# Daughter_Card_v7_fixed.net
KiCad netlist of a schematic drawn in EAGLE
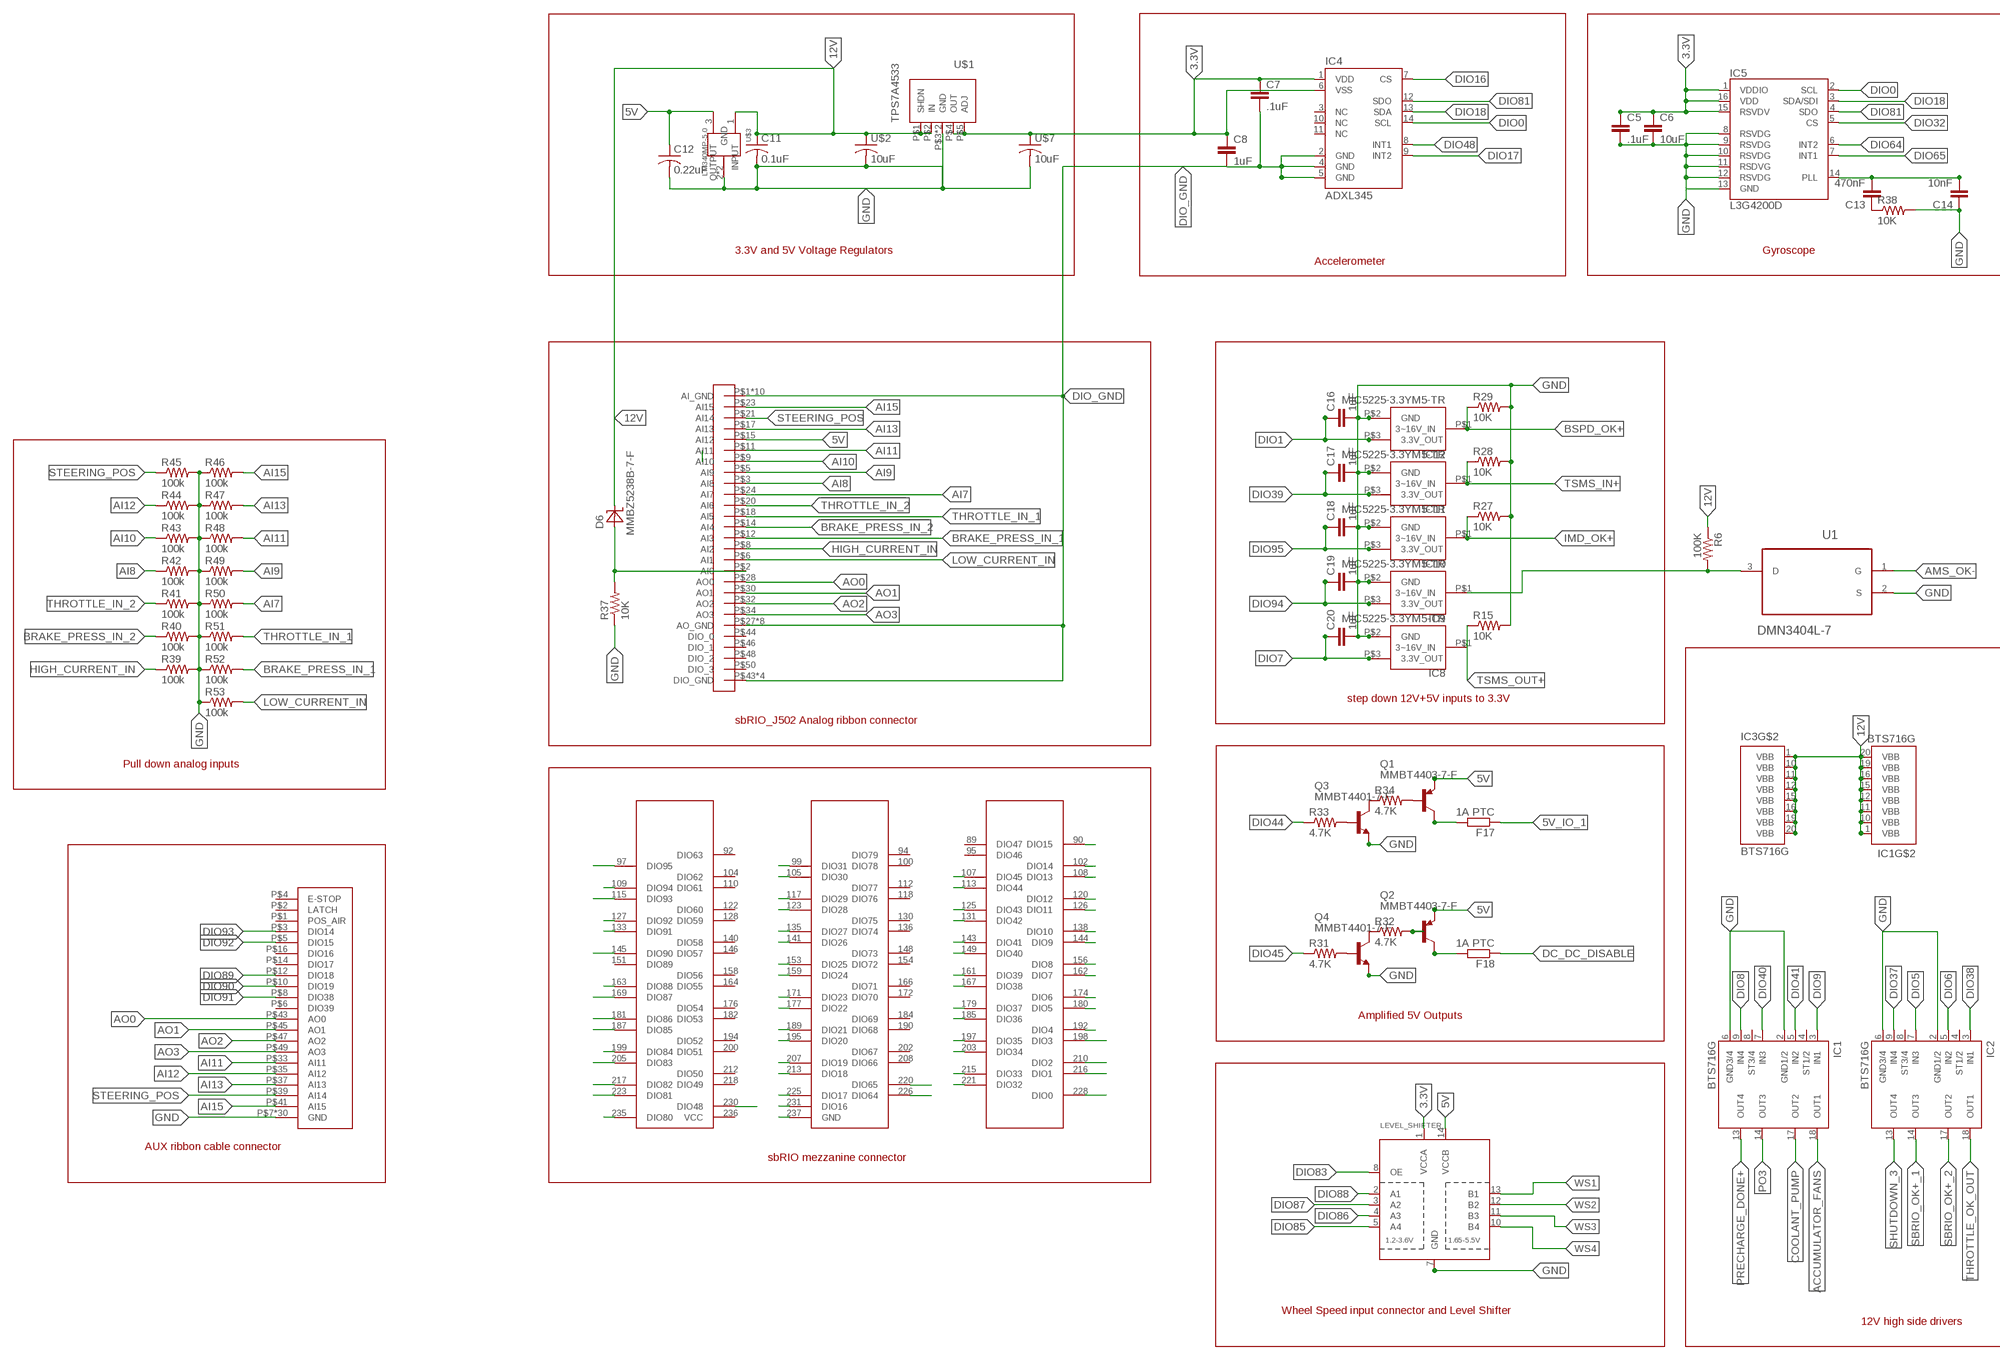
[diagram p0: schematic, sheet 1, part 1 of 2]
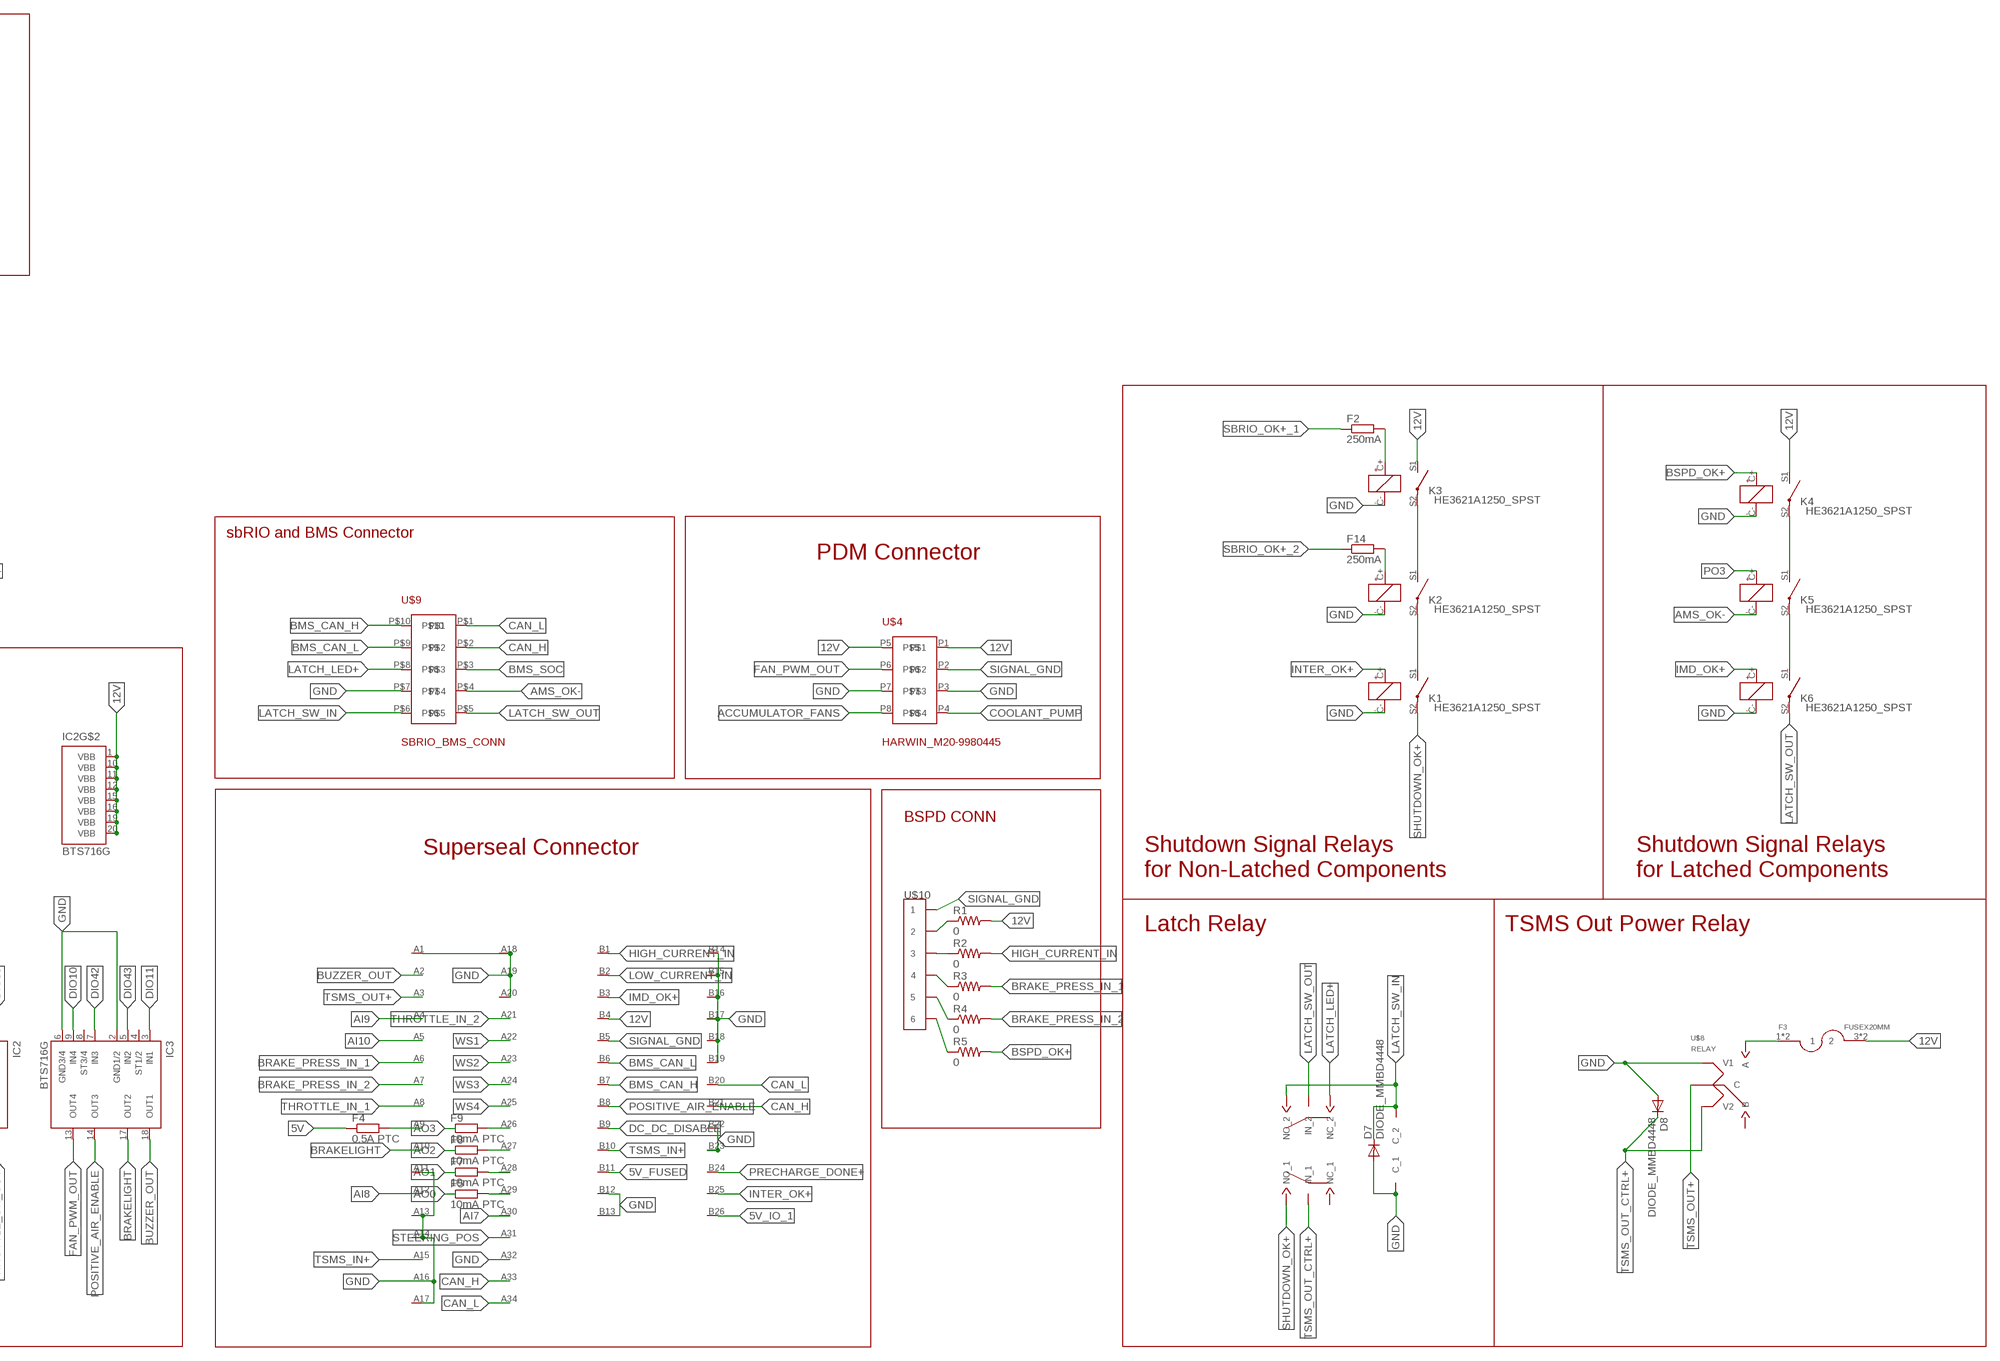
[diagram p1: schematic, sheet 1, part 2 of 2]

(export (version "E")
  (design (tool "Eeschema 10.0.6"))
  (components
    (comp (ref "C5")
      (value ".1uF")
      (footprint "eagle-import:0603-CAP")
      (libsource (lib "eagle-import") (part "CAP0603-CAP"))
    )
    (comp (ref "C6")
      (value "10uF")
      (footprint "eagle-import:0603-CAP")
      (libsource (lib "eagle-import") (part "CAP0603-CAP"))
    )
    (comp (ref "C7")
      (value ".1uF")
      (footprint "eagle-import:0603-CAP")
      (libsource (lib "eagle-import") (part "CAP0603-CAP"))
    )
    (comp (ref "C8")
      (value "1uF")
      (footprint "eagle-import:0603-CAP")
      (libsource (lib "eagle-import") (part "CAP0603-CAP"))
    )
    (comp (ref "C11")
      (value "0.1uF")
      (footprint "eagle-import:C1206")
      (libsource (lib "eagle-import") (part "C-USC1206"))
    )
    (comp (ref "C12")
      (value "0.22uF")
      (footprint "eagle-import:C1206")
      (libsource (lib "eagle-import") (part "C-USC1206"))
    )
    (comp (ref "C13")
      (value "470nF")
      (footprint "eagle-import:0603-CAP")
      (libsource (lib "eagle-import") (part "CAP0603-CAP"))
    )
    (comp (ref "C14")
      (value "10nF")
      (footprint "eagle-import:0603-CAP")
      (libsource (lib "eagle-import") (part "CAP0603-CAP"))
    )
    (comp (ref "C16")
      (value "1uF")
      (footprint "eagle-import:0603-CAP")
      (libsource (lib "eagle-import") (part "CAP0603-CAP"))
    )
    (comp (ref "C17")
      (value "1uF")
      (footprint "eagle-import:0603-CAP")
      (libsource (lib "eagle-import") (part "CAP0603-CAP"))
    )
    (comp (ref "C18")
      (value "1uF")
      (footprint "eagle-import:0603-CAP")
      (libsource (lib "eagle-import") (part "CAP0603-CAP"))
    )
    (comp (ref "C19")
      (value "1uF")
      (footprint "eagle-import:0603-CAP")
      (libsource (lib "eagle-import") (part "CAP0603-CAP"))
    )
    (comp (ref "C20")
      (value "1uF")
      (footprint "eagle-import:0603-CAP")
      (libsource (lib "eagle-import") (part "CAP0603-CAP"))
    )
    (comp (ref "D6")
      (value "MMBZ5238B-7-F")
      (footprint "eagle-import:SOT-23-3")
      (libsource (lib "eagle-import") (part "MMBZ5238B-7-F"))
    )
    (comp (ref "D7")
      (value "DIODE_MMBD4448")
      (footprint "eagle-import:SOT-23-3")
      (libsource (lib "eagle-import") (part "DIODE_MMBD4448"))
    )
    (comp (ref "D8")
      (value "DIODE_MMBD4448")
      (footprint "eagle-import:SOT-23-3")
      (libsource (lib "eagle-import") (part "DIODE_MMBD4448"))
    )
    (comp (ref "F2")
      (value "250mA")
      (footprint "eagle-import:R0603")
      (libsource (lib "eagle-import") (part "R-EU_R0603"))
    )
    (comp (ref "F3")
      (value "FUSEX20MM")
      (footprint "eagle-import:FUSE_5MM")
      (libsource (lib "eagle-import") (part "FUSEX20MM"))
    )
    (comp (ref "F4")
      (value "0.5A PTC")
      (footprint "eagle-import:R0603")
      (libsource (lib "eagle-import") (part "R-EU_R0603"))
    )
    (comp (ref "F5")
      (value "10mA PTC")
      (footprint "eagle-import:R0603")
      (libsource (lib "eagle-import") (part "R-EU_R0603"))
    )
    (comp (ref "F7")
      (value "10mA PTC")
      (footprint "eagle-import:R0603")
      (libsource (lib "eagle-import") (part "R-EU_R0603"))
    )
    (comp (ref "F8")
      (value "10mA PTC")
      (footprint "eagle-import:R0603")
      (libsource (lib "eagle-import") (part "R-EU_R0603"))
    )
    (comp (ref "F9")
      (value "10mA PTC")
      (footprint "eagle-import:R0603")
      (libsource (lib "eagle-import") (part "R-EU_R0603"))
    )
    (comp (ref "F14")
      (value "250mA")
      (footprint "eagle-import:R0603")
      (libsource (lib "eagle-import") (part "R-EU_R0603"))
    )
    (comp (ref "F17")
      (value "1A PTC")
      (footprint "eagle-import:R0603")
      (libsource (lib "eagle-import") (part "R-EU_R0603"))
    )
    (comp (ref "F18")
      (value "1A PTC")
      (footprint "eagle-import:R0603")
      (libsource (lib "eagle-import") (part "R-EU_R0603"))
    )
    (comp (ref "IC1")
      (value "BTS716G")
      (footprint "eagle-import:PG-DSO-20")
      (libsource (lib "eagle-import") (part "BTS716G"))
    )
    (comp (ref "IC2")
      (value "BTS716G")
      (footprint "eagle-import:PG-DSO-20")
      (libsource (lib "eagle-import") (part "BTS716G"))
    )
    (comp (ref "IC3")
      (value "BTS716G")
      (footprint "eagle-import:PG-DSO-20")
      (libsource (lib "eagle-import") (part "BTS716G"))
    )
    (comp (ref "IC4")
      (value "ADXL345")
      (footprint "eagle-import:LGA14")
      (libsource (lib "eagle-import") (part "ADXL345"))
    )
    (comp (ref "IC5")
      (value "L3G4200D")
      (footprint "eagle-import:LGA16-4X4")
      (libsource (lib "eagle-import") (part "L3G4200D"))
    )
    (comp (ref "IC8")
      (value "MIC5225-3.3YM5-TR")
      (footprint "eagle-import:SOT-23-3")
      (libsource (lib "eagle-import") (part "MIC5225-3.3YM5-TR"))
    )
    (comp (ref "IC9")
      (value "MIC5225-3.3YM5-TR")
      (footprint "eagle-import:SOT-23-3")
      (libsource (lib "eagle-import") (part "MIC5225-3.3YM5-TR"))
    )
    (comp (ref "IC10")
      (value "MIC5225-3.3YM5-TR")
      (footprint "eagle-import:SOT-23-3")
      (libsource (lib "eagle-import") (part "MIC5225-3.3YM5-TR"))
    )
    (comp (ref "IC11")
      (value "MIC5225-3.3YM5-TR")
      (footprint "eagle-import:SOT-23-3")
      (libsource (lib "eagle-import") (part "MIC5225-3.3YM5-TR"))
    )
    (comp (ref "IC12")
      (value "MIC5225-3.3YM5-TR")
      (footprint "eagle-import:SOT-23-3")
      (libsource (lib "eagle-import") (part "MIC5225-3.3YM5-TR"))
    )
    (comp (ref "K1")
      (value "HE3621A1250_SPST")
      (footprint "eagle-import:HE3621A1250_SPST")
      (libsource (lib "eagle-import") (part "HE3621A1250_SPST"))
    )
    (comp (ref "K2")
      (value "HE3621A1250_SPST")
      (footprint "eagle-import:HE3621A1250_SPST")
      (libsource (lib "eagle-import") (part "HE3621A1250_SPST"))
    )
    (comp (ref "K3")
      (value "HE3621A1250_SPST")
      (footprint "eagle-import:HE3621A1250_SPST")
      (libsource (lib "eagle-import") (part "HE3621A1250_SPST"))
    )
    (comp (ref "K4")
      (value "HE3621A1250_SPST")
      (footprint "eagle-import:HE3621A1250_SPST")
      (libsource (lib "eagle-import") (part "HE3621A1250_SPST"))
    )
    (comp (ref "K5")
      (value "HE3621A1250_SPST")
      (footprint "eagle-import:HE3621A1250_SPST")
      (libsource (lib "eagle-import") (part "HE3621A1250_SPST"))
    )
    (comp (ref "K6")
      (value "HE3621A1250_SPST")
      (footprint "eagle-import:HE3621A1250_SPST")
      (libsource (lib "eagle-import") (part "HE3621A1250_SPST"))
    )
    (comp (ref "LATCH_U7")
      (value "JW2SN-DC12V")
      (footprint "eagle-import:DPDT_JW2_FORM_C")
      (libsource (lib "eagle-import") (part "JW2SN-DC12V"))
    )
    (comp (ref "LEVEL_SHIFTER")
      (value "TXB0104PWR")
      (footprint "eagle-import:TSSOP14")
      (libsource (lib "eagle-import") (part "TXB0104PWR"))
    )
    (comp (ref "Q1")
      (value "MMBT4403-7-F")
      (footprint "eagle-import:SOT-23-3")
      (libsource (lib "eagle-import") (part "MMBT4403-7-F"))
    )
    (comp (ref "Q2")
      (value "MMBT4403-7-F")
      (footprint "eagle-import:SOT-23-3")
      (libsource (lib "eagle-import") (part "MMBT4403-7-F"))
    )
    (comp (ref "Q3")
      (value "MMBT4401-7-F")
      (footprint "eagle-import:SOT-23-3")
      (libsource (lib "eagle-import") (part "MMBT4401-7-F"))
    )
    (comp (ref "Q4")
      (value "MMBT4401-7-F")
      (footprint "eagle-import:SOT-23-3")
      (libsource (lib "eagle-import") (part "MMBT4401-7-F"))
    )
    (comp (ref "R1")
      (value "0")
      (footprint "eagle-import:M0805")
      (libsource (lib "eagle-import") (part "resistor_R-US_M0805"))
    )
    (comp (ref "R2")
      (value "0")
      (footprint "eagle-import:M0805")
      (libsource (lib "eagle-import") (part "resistor_R-US_M0805"))
    )
    (comp (ref "R3")
      (value "0")
      (footprint "eagle-import:M0805")
      (libsource (lib "eagle-import") (part "resistor_R-US_M0805"))
    )
    (comp (ref "R4")
      (value "0")
      (footprint "eagle-import:M0805")
      (libsource (lib "eagle-import") (part "resistor_R-US_M0805"))
    )
    (comp (ref "R5")
      (value "0")
      (footprint "eagle-import:M0805")
      (libsource (lib "eagle-import") (part "resistor_R-US_M0805"))
    )
    (comp (ref "R6")
      (value "100K")
      (footprint "eagle-import:R0603")
      (libsource (lib "eagle-import") (part "R-US_R0603"))
    )
    (comp (ref "R15")
      (value "10K")
      (footprint "eagle-import:R0603")
      (libsource (lib "eagle-import") (part "resistor_R-US_R0603"))
    )
    (comp (ref "R27")
      (value "10K")
      (footprint "eagle-import:R0603")
      (libsource (lib "eagle-import") (part "resistor_R-US_R0603"))
    )
    (comp (ref "R28")
      (value "10K")
      (footprint "eagle-import:R0603")
      (libsource (lib "eagle-import") (part "resistor_R-US_R0603"))
    )
    (comp (ref "R29")
      (value "10K")
      (footprint "eagle-import:R0603")
      (libsource (lib "eagle-import") (part "resistor_R-US_R0603"))
    )
    (comp (ref "R31")
      (value "4.7K")
      (footprint "eagle-import:R0603")
      (libsource (lib "eagle-import") (part "resistor_R-US_R0603"))
    )
    (comp (ref "R32")
      (value "4.7K")
      (footprint "eagle-import:R0603")
      (libsource (lib "eagle-import") (part "resistor_R-US_R0603"))
    )
    (comp (ref "R33")
      (value "4.7K")
      (footprint "eagle-import:R0603")
      (libsource (lib "eagle-import") (part "resistor_R-US_R0603"))
    )
    (comp (ref "R34")
      (value "4.7K")
      (footprint "eagle-import:R0603")
      (libsource (lib "eagle-import") (part "resistor_R-US_R0603"))
    )
    (comp (ref "R37")
      (value "10K")
      (footprint "eagle-import:R0603")
      (libsource (lib "eagle-import") (part "resistor_R-US_R0603"))
    )
    (comp (ref "R38")
      (value "10K")
      (footprint "eagle-import:R0603")
      (libsource (lib "eagle-import") (part "resistor_R-US_R0603"))
    )
    (comp (ref "R39")
      (value "100k")
      (footprint "eagle-import:R0603")
      (libsource (lib "eagle-import") (part "resistor_R-US_R0603"))
    )
    (comp (ref "R40")
      (value "100k")
      (footprint "eagle-import:R0603")
      (libsource (lib "eagle-import") (part "resistor_R-US_R0603"))
    )
    (comp (ref "R41")
      (value "100k")
      (footprint "eagle-import:R0603")
      (libsource (lib "eagle-import") (part "resistor_R-US_R0603"))
    )
    (comp (ref "R42")
      (value "100k")
      (footprint "eagle-import:R0603")
      (libsource (lib "eagle-import") (part "resistor_R-US_R0603"))
    )
    (comp (ref "R43")
      (value "100k")
      (footprint "eagle-import:R0603")
      (libsource (lib "eagle-import") (part "resistor_R-US_R0603"))
    )
    (comp (ref "R44")
      (value "100k")
      (footprint "eagle-import:R0603")
      (libsource (lib "eagle-import") (part "resistor_R-US_R0603"))
    )
    (comp (ref "R45")
      (value "100k")
      (footprint "eagle-import:R0603")
      (libsource (lib "eagle-import") (part "resistor_R-US_R0603"))
    )
    (comp (ref "R46")
      (value "100k")
      (footprint "eagle-import:R0603")
      (libsource (lib "eagle-import") (part "resistor_R-US_R0603"))
    )
    (comp (ref "R47")
      (value "100k")
      (footprint "eagle-import:R0603")
      (libsource (lib "eagle-import") (part "resistor_R-US_R0603"))
    )
    (comp (ref "R48")
      (value "100k")
      (footprint "eagle-import:R0603")
      (libsource (lib "eagle-import") (part "resistor_R-US_R0603"))
    )
    (comp (ref "R49")
      (value "100k")
      (footprint "eagle-import:R0603")
      (libsource (lib "eagle-import") (part "resistor_R-US_R0603"))
    )
    (comp (ref "R50")
      (value "100k")
      (footprint "eagle-import:R0603")
      (libsource (lib "eagle-import") (part "resistor_R-US_R0603"))
    )
    (comp (ref "R51")
      (value "100k")
      (footprint "eagle-import:R0603")
      (libsource (lib "eagle-import") (part "resistor_R-US_R0603"))
    )
    (comp (ref "R52")
      (value "100k")
      (footprint "eagle-import:R0603")
      (libsource (lib "eagle-import") (part "resistor_R-US_R0603"))
    )
    (comp (ref "R53")
      (value "100k")
      (footprint "eagle-import:R0603")
      (libsource (lib "eagle-import") (part "resistor_R-US_R0603"))
    )
    (comp (ref "SBRIO_ANALOG")
      (value "SBRIO_MIO")
      (footprint "eagle-import:SBRIO_J502_J503")
      (libsource (lib "eagle-import") (part "SBRIO_MIO"))
    )
    (comp (ref "SBRIO_AUX")
      (value "SBRIO_AUX")
      (footprint "eagle-import:SBRIO_J502_J503")
      (libsource (lib "eagle-import") (part "SBRIO_AUX"))
    )
    (comp (ref "SBRIO_MEZZANINE")
      (value "SBRIO_RMC")
      (footprint "eagle-import:SEAM-40-XX.X-XX-06-X-A")
      (libsource (lib "eagle-import") (part "SBRIO_RMC"))
    )
    (comp (ref "U$1")
      (value "TPS7A4533")
      (footprint "eagle-import:TPS7A4533")
      (libsource (lib "eagle-import") (part "TPS7A4533"))
    )
    (comp (ref "U$2")
      (value "10uF")
      (footprint "eagle-import:C1206")
      (libsource (lib "eagle-import") (part "C-USC1206"))
    )
    (comp (ref "U$3")
      (value "LM340MP-5.0")
      (footprint "eagle-import:SOT-223-4")
      (libsource (lib "eagle-import") (part "LM340MP-5.0"))
    )
    (comp (ref "U$4")
      (value "HARWIN_M20-9980445")
      (footprint "eagle-import:HARWIN_M20-9980445")
      (libsource (lib "eagle-import") (part "HARWIN_M20-9980445"))
    )
    (comp (ref "U$6")
      (value "SUPERSEAL1.0_60POS")
      (footprint "eagle-import:SUPERSEAL1.0_60POS")
      (libsource (lib "eagle-import") (part "SUPERSEAL1.0_60POS"))
    )
    (comp (ref "U$7")
      (value "10uF")
      (footprint "eagle-import:C1206")
      (libsource (lib "eagle-import") (part "C-USC1206"))
    )
    (comp (ref "U$8")
      (value "RELAY")
      (footprint "eagle-import:RELAY")
      (libsource (lib "eagle-import") (part "RELAY"))
    )
    (comp (ref "U$9")
      (value "SBRIO_BMS_CONN")
      (footprint "eagle-import:SBRIO_W")
      (libsource (lib "eagle-import") (part "SBRIO_BMS_CONN"))
    )
    (comp (ref "U$10")
      (value "SULLINS_1MM_6P_HEADER")
      (footprint "eagle-import:SULLINS_1MM_HEADER")
      (libsource (lib "eagle-import") (part "SULLINS_1MM_6P_HEADER"))
    )
    (comp (ref "U1")
      (value "DMN3404L-7")
      (footprint "eagle-import:SOT95P235X112-3N")
      (libsource (lib "eagle-import") (part "DMN3404L-7"))
    )
  )
  (nets
    (net (code "1") (name "/VCC") (class "Default")
      (node (ref "SBRIO_MEZZANINE") (pin "236") (pinfunction "VCC_236") (pintype "power_in"))
    )
    (net (code "2") (name "3.3V") (class "Default")
      (node (ref "C5") (pin "1") (pinfunction "1_1") (pintype "passive"))
      (node (ref "C6") (pin "1") (pinfunction "1_1") (pintype "passive"))
      (node (ref "C7") (pin "1") (pinfunction "1_1") (pintype "passive"))
      (node (ref "C8") (pin "1") (pinfunction "1_1") (pintype "passive"))
      (node (ref "IC4") (pin "1") (pinfunction "VDD_1") (pintype "bidirectional"))
      (node (ref "IC4") (pin "6") (pinfunction "VSS_6") (pintype "bidirectional"))
      (node (ref "IC5") (pin "1") (pinfunction "VDDIO_1") (pintype "bidirectional"))
      (node (ref "IC5") (pin "15") (pinfunction "RSVDV_15") (pintype "bidirectional"))
      (node (ref "IC5") (pin "16") (pinfunction "VDD_16") (pintype "bidirectional"))
      (node (ref "LEVEL_SHIFTER") (pin "1") (pinfunction "VCCA_1") (pintype "bidirectional"))
      (node (ref "U$1") (pin "P$4") (pinfunction "OUT_P$4") (pintype "bidirectional"))
      (node (ref "U$1") (pin "P$5") (pinfunction "ADJ_P$5") (pintype "bidirectional"))
      (node (ref "U$7") (pin "1") (pinfunction "1_1") (pintype "passive"))
    )
    (net (code "3") (name "5V") (class "Default")
      (node (ref "C12") (pin "1") (pinfunction "1_1") (pintype "passive"))
      (node (ref "F4") (pin "1") (pinfunction "1_1") (pintype "passive"))
      (node (ref "LEVEL_SHIFTER") (pin "14") (pinfunction "VCCB_14") (pintype "bidirectional"))
      (node (ref "Q1") (pin "P$3") (pinfunction "E_P$3") (pintype "passive"))
      (node (ref "Q2") (pin "P$3") (pinfunction "E_P$3") (pintype "passive"))
      (node (ref "SBRIO_ANALOG") (pin "P$15") (pinfunction "AI12_P$15") (pintype "input"))
      (node (ref "U$3") (pin "3") (pinfunction "OUTPUT_3") (pintype "bidirectional"))
    )
    (net (code "4") (name "5V_FUSED") (class "Default")
      (node (ref "F4") (pin "2") (pinfunction "2_2") (pintype "passive"))
      (node (ref "U$6") (pin "A9") (pinfunction "A9_A9") (pintype "bidirectional"))
      (node (ref "U$6") (pin "B11") (pinfunction "B11_B11") (pintype "bidirectional"))
    )
    (net (code "5") (name "5V_IO_1") (class "Default")
      (node (ref "F17") (pin "1") (pinfunction "1_1") (pintype "passive"))
      (node (ref "U$6") (pin "B26") (pinfunction "B26_B26") (pintype "bidirectional"))
    )
    (net (code "6") (name "12V") (class "Default")
      (node (ref "C11") (pin "1") (pinfunction "1_1") (pintype "passive"))
      (node (ref "D6") (pin "P$1") (pinfunction "C_P$1") (pintype "passive"))
      (node (ref "F3") (pin "3") (pinfunction "2_3") (pintype "bidirectional"))
      (node (ref "F3") (pin "4") (pinfunction "2_4") (pintype "bidirectional"))
      (node (ref "IC1") (pin "1") (pinfunction "VBB_1") (pintype "power_in"))
      (node (ref "IC1") (pin "10") (pinfunction "VBB_10") (pintype "power_in"))
      (node (ref "IC1") (pin "11") (pinfunction "VBB_11") (pintype "power_in"))
      (node (ref "IC1") (pin "12") (pinfunction "VBB_12") (pintype "power_in"))
      (node (ref "IC1") (pin "15") (pinfunction "VBB_15") (pintype "power_in"))
      (node (ref "IC1") (pin "16") (pinfunction "VBB_16") (pintype "power_in"))
      (node (ref "IC1") (pin "19") (pinfunction "VBB_19") (pintype "power_in"))
      (node (ref "IC1") (pin "20") (pinfunction "VBB_20") (pintype "power_in"))
      (node (ref "IC2") (pin "1") (pinfunction "VBB_1") (pintype "power_in"))
      (node (ref "IC2") (pin "10") (pinfunction "VBB_10") (pintype "power_in"))
      (node (ref "IC2") (pin "11") (pinfunction "VBB_11") (pintype "power_in"))
      (node (ref "IC2") (pin "12") (pinfunction "VBB_12") (pintype "power_in"))
      (node (ref "IC2") (pin "15") (pinfunction "VBB_15") (pintype "power_in"))
      (node (ref "IC2") (pin "16") (pinfunction "VBB_16") (pintype "power_in"))
      (node (ref "IC2") (pin "19") (pinfunction "VBB_19") (pintype "power_in"))
      (node (ref "IC2") (pin "20") (pinfunction "VBB_20") (pintype "power_in"))
      (node (ref "IC3") (pin "1") (pinfunction "VBB_1") (pintype "power_in"))
      (node (ref "IC3") (pin "10") (pinfunction "VBB_10") (pintype "power_in"))
      (node (ref "IC3") (pin "11") (pinfunction "VBB_11") (pintype "power_in"))
      (node (ref "IC3") (pin "12") (pinfunction "VBB_12") (pintype "power_in"))
      (node (ref "IC3") (pin "15") (pinfunction "VBB_15") (pintype "power_in"))
      (node (ref "IC3") (pin "16") (pinfunction "VBB_16") (pintype "power_in"))
      (node (ref "IC3") (pin "19") (pinfunction "VBB_19") (pintype "power_in"))
      (node (ref "IC3") (pin "20") (pinfunction "VBB_20") (pintype "power_in"))
      (node (ref "K3") (pin "S1") (pinfunction "SW_1_S1") (pintype "passive"))
      (node (ref "K4") (pin "S1") (pinfunction "SW_1_S1") (pintype "passive"))
      (node (ref "R1") (pin "2") (pinfunction "2_2") (pintype "passive"))
      (node (ref "R6") (pin "1") (pinfunction "1_1") (pintype "passive"))
      (node (ref "U$1") (pin "P$1") (pinfunction "SHDN_P$1") (pintype "bidirectional"))
      (node (ref "U$1") (pin "P$2") (pinfunction "IN_P$2") (pintype "bidirectional"))
      (node (ref "U$2") (pin "1") (pinfunction "1_1") (pintype "passive"))
      (node (ref "U$3") (pin "1") (pinfunction "INPUT_1") (pintype "bidirectional"))
      (node (ref "U$4") (pin "P1") (pinfunction "P$1_P1") (pintype "bidirectional"))
      (node (ref "U$4") (pin "P5") (pinfunction "P$5_P5") (pintype "bidirectional"))
      (node (ref "U$6") (pin "B4") (pinfunction "B4_B4") (pintype "bidirectional"))
    )
    (net (code "7") (name "ACCUMULATOR_FANS") (class "Default")
      (node (ref "IC1") (pin "18") (pinfunction "OUT1_18") (pintype "output"))
      (node (ref "U$4") (pin "P8") (pinfunction "P$8_P8") (pintype "bidirectional"))
    )
    (net (code "8") (name "AI7") (class "Default")
      (node (ref "R50") (pin "2") (pinfunction "2_2") (pintype "passive"))
      (node (ref "SBRIO_ANALOG") (pin "P$24") (pinfunction "AI7_P$24") (pintype "input"))
      (node (ref "U$6") (pin "A30") (pinfunction "A30_A30") (pintype "bidirectional"))
    )
    (net (code "9") (name "AI8") (class "Default")
      (node (ref "R42") (pin "1") (pinfunction "1_1") (pintype "passive"))
      (node (ref "SBRIO_ANALOG") (pin "P$3") (pinfunction "AI8_P$3") (pintype "input"))
      (node (ref "U$6") (pin "A12") (pinfunction "A12_A12") (pintype "bidirectional"))
    )
    (net (code "10") (name "AI9") (class "Default")
      (node (ref "R49") (pin "2") (pinfunction "2_2") (pintype "passive"))
      (node (ref "SBRIO_ANALOG") (pin "P$5") (pinfunction "AI9_P$5") (pintype "input"))
      (node (ref "U$6") (pin "A4") (pinfunction "A4_A4") (pintype "bidirectional"))
    )
    (net (code "11") (name "AI10") (class "Default")
      (node (ref "R43") (pin "1") (pinfunction "1_1") (pintype "passive"))
      (node (ref "SBRIO_ANALOG") (pin "P$9") (pinfunction "AI10_P$9") (pintype "input"))
      (node (ref "U$6") (pin "A5") (pinfunction "A5_A5") (pintype "bidirectional"))
    )
    (net (code "12") (name "AI11") (class "Default")
      (node (ref "R48") (pin "2") (pinfunction "2_2") (pintype "passive"))
      (node (ref "SBRIO_ANALOG") (pin "P$11") (pinfunction "AI11_P$11") (pintype "input"))
      (node (ref "SBRIO_AUX") (pin "P$33") (pinfunction "AI11_P$33") (pintype "bidirectional"))
    )
    (net (code "13") (name "AI12") (class "Default")
      (node (ref "R44") (pin "1") (pinfunction "1_1") (pintype "passive"))
      (node (ref "SBRIO_AUX") (pin "P$35") (pinfunction "AI12_P$35") (pintype "bidirectional"))
    )
    (net (code "14") (name "AI13") (class "Default")
      (node (ref "R47") (pin "2") (pinfunction "2_2") (pintype "passive"))
      (node (ref "SBRIO_ANALOG") (pin "P$17") (pinfunction "AI13_P$17") (pintype "input"))
      (node (ref "SBRIO_AUX") (pin "P$37") (pinfunction "AI13_P$37") (pintype "bidirectional"))
    )
    (net (code "15") (name "AI15") (class "Default")
      (node (ref "R46") (pin "2") (pinfunction "2_2") (pintype "passive"))
      (node (ref "SBRIO_ANALOG") (pin "P$23") (pinfunction "AI15_P$23") (pintype "input"))
      (node (ref "SBRIO_AUX") (pin "P$41") (pinfunction "AI15_P$41") (pintype "bidirectional"))
    )
    (net (code "16") (name "AMS_OK-") (class "Default")
      (node (ref "K5") (pin "C-") (pinfunction "C-_C-") (pintype "passive"))
      (node (ref "U$9") (pin "P$4") (pinfunction "P$4_P$4") (pintype "bidirectional"))
      (node (ref "U1") (pin "1") (pinfunction "G_1") (pintype "input"))
    )
    (net (code "17") (name "AO0") (class "Default")
      (node (ref "F5") (pin "1") (pinfunction "1_1") (pintype "passive"))
      (node (ref "SBRIO_ANALOG") (pin "P$28") (pinfunction "AO0_P$28") (pintype "output"))
      (node (ref "SBRIO_AUX") (pin "P$43") (pinfunction "AO0_P$43") (pintype "bidirectional"))
    )
    (net (code "18") (name "AO1") (class "Default")
      (node (ref "F7") (pin "1") (pinfunction "1_1") (pintype "passive"))
      (node (ref "SBRIO_ANALOG") (pin "P$30") (pinfunction "AO1_P$30") (pintype "output"))
      (node (ref "SBRIO_AUX") (pin "P$45") (pinfunction "AO1_P$45") (pintype "bidirectional"))
    )
    (net (code "19") (name "AO2") (class "Default")
      (node (ref "F8") (pin "1") (pinfunction "1_1") (pintype "passive"))
      (node (ref "SBRIO_ANALOG") (pin "P$32") (pinfunction "AO2_P$32") (pintype "output"))
      (node (ref "SBRIO_AUX") (pin "P$47") (pinfunction "AO2_P$47") (pintype "bidirectional"))
    )
    (net (code "20") (name "AO3") (class "Default")
      (node (ref "F9") (pin "1") (pinfunction "1_1") (pintype "passive"))
      (node (ref "SBRIO_ANALOG") (pin "P$34") (pinfunction "AO3_P$34") (pintype "output"))
      (node (ref "SBRIO_AUX") (pin "P$49") (pinfunction "AO3_P$49") (pintype "bidirectional"))
    )
    (net (code "21") (name "BMS_CAN_H") (class "Default")
      (node (ref "U$6") (pin "B7") (pinfunction "B7_B7") (pintype "bidirectional"))
      (node (ref "U$9") (pin "P$10") (pinfunction "P$10_P$10") (pintype "bidirectional"))
    )
    (net (code "22") (name "BMS_CAN_L") (class "Default")
      (node (ref "U$6") (pin "B6") (pinfunction "B6_B6") (pintype "bidirectional"))
      (node (ref "U$9") (pin "P$9") (pinfunction "P$9_P$9") (pintype "bidirectional"))
    )
    (net (code "23") (name "BMS_SOC") (class "Default")
      (node (ref "U$9") (pin "P$3") (pinfunction "P$3_P$3") (pintype "bidirectional"))
    )
    (net (code "24") (name "BRAKELIGHT") (class "Default")
      (node (ref "IC3") (pin "17") (pinfunction "OUT2_17") (pintype "output"))
      (node (ref "U$6") (pin "A10") (pinfunction "A10_A10") (pintype "bidirectional"))
    )
    (net (code "25") (name "BRAKE_PRESS_IN_1") (class "Default")
      (node (ref "R3") (pin "2") (pinfunction "2_2") (pintype "passive"))
      (node (ref "R52") (pin "2") (pinfunction "2_2") (pintype "passive"))
      (node (ref "SBRIO_ANALOG") (pin "P$12") (pinfunction "AI3_P$12") (pintype "input"))
      (node (ref "U$6") (pin "A6") (pinfunction "A6_A6") (pintype "bidirectional"))
    )
    (net (code "26") (name "BRAKE_PRESS_IN_2") (class "Default")
      (node (ref "R4") (pin "2") (pinfunction "2_2") (pintype "passive"))
      (node (ref "R40") (pin "1") (pinfunction "1_1") (pintype "passive"))
      (node (ref "SBRIO_ANALOG") (pin "P$14") (pinfunction "AI4_P$14") (pintype "input"))
      (node (ref "U$6") (pin "A7") (pinfunction "A7_A7") (pintype "bidirectional"))
    )
    (net (code "27") (name "BSPD_OK+") (class "Default")
      (node (ref "IC12") (pin "P$1") (pinfunction "3~{16V_IN}_P$1") (pintype "bidirectional"))
      (node (ref "K4") (pin "C+") (pinfunction "C+_C+") (pintype "passive"))
      (node (ref "R29") (pin "1") (pinfunction "1_1") (pintype "passive"))
      (node (ref "R5") (pin "2") (pinfunction "2_2") (pintype "passive"))
    )
    (net (code "28") (name "BUZZER_OUT") (class "Default")
      (node (ref "IC3") (pin "18") (pinfunction "OUT1_18") (pintype "output"))
      (node (ref "U$6") (pin "A2") (pinfunction "A2_A2") (pintype "bidirectional"))
    )
    (net (code "29") (name "CAN_H") (class "Default")
      (node (ref "U$6") (pin "A33") (pinfunction "A33_A33") (pintype "bidirectional"))
      (node (ref "U$6") (pin "B21") (pinfunction "B21_B21") (pintype "bidirectional"))
      (node (ref "U$9") (pin "P$2") (pinfunction "P$2_P$2") (pintype "bidirectional"))
    )
    (net (code "30") (name "CAN_L") (class "Default")
      (node (ref "U$6") (pin "A34") (pinfunction "A34_A34") (pintype "bidirectional"))
      (node (ref "U$6") (pin "B20") (pinfunction "B20_B20") (pintype "bidirectional"))
      (node (ref "U$9") (pin "P$1") (pinfunction "P$1_P$1") (pintype "bidirectional"))
    )
    (net (code "31") (name "COOLANT_PUMP") (class "Default")
      (node (ref "IC1") (pin "17") (pinfunction "OUT2_17") (pintype "output"))
      (node (ref "U$4") (pin "P4") (pinfunction "P$4_P4") (pintype "bidirectional"))
    )
    (net (code "32") (name "DC_DC_DISABLE") (class "Default")
      (node (ref "F18") (pin "1") (pinfunction "1_1") (pintype "passive"))
      (node (ref "U$6") (pin "B9") (pinfunction "B9_B9") (pintype "bidirectional"))
    )
    (net (code "33") (name "DIO0") (class "Default")
      (node (ref "IC4") (pin "14") (pinfunction "SCL_14") (pintype "bidirectional"))
      (node (ref "IC5") (pin "2") (pinfunction "SCL_2") (pintype "bidirectional"))
      (node (ref "SBRIO_MEZZANINE") (pin "228") (pinfunction "DIO0_228") (pintype "bidirectional"))
    )
    (net (code "34") (name "DIO1") (class "Default")
      (node (ref "C16") (pin "1") (pinfunction "1_1") (pintype "passive"))
      (node (ref "IC12") (pin "P$3") (pinfunction "3.3V_OUT_P$3") (pintype "bidirectional"))
      (node (ref "SBRIO_MEZZANINE") (pin "216") (pinfunction "DIO1_216") (pintype "bidirectional"))
    )
    (net (code "35") (name "DIO5") (class "Default")
      (node (ref "IC2") (pin "7") (pinfunction "IN3_7") (pintype "input"))
      (node (ref "SBRIO_MEZZANINE") (pin "180") (pinfunction "DIO5_180") (pintype "bidirectional"))
    )
    (net (code "36") (name "DIO6") (class "Default")
      (node (ref "IC2") (pin "5") (pinfunction "IN2_5") (pintype "input"))
      (node (ref "SBRIO_MEZZANINE") (pin "174") (pinfunction "DIO6_174") (pintype "bidirectional"))
    )
    (net (code "37") (name "DIO7") (class "Default")
      (node (ref "C20") (pin "1") (pinfunction "1_1") (pintype "passive"))
      (node (ref "IC8") (pin "P$3") (pinfunction "3.3V_OUT_P$3") (pintype "bidirectional"))
      (node (ref "SBRIO_MEZZANINE") (pin "162") (pinfunction "DIO7_162") (pintype "bidirectional"))
    )
    (net (code "38") (name "DIO8") (class "Default")
      (node (ref "IC1") (pin "9") (pinfunction "IN4_9") (pintype "input"))
      (node (ref "SBRIO_MEZZANINE") (pin "156") (pinfunction "DIO8_156") (pintype "bidirectional"))
    )
    (net (code "39") (name "DIO9") (class "Default")
      (node (ref "IC1") (pin "3") (pinfunction "IN1_3") (pintype "input"))
      (node (ref "SBRIO_MEZZANINE") (pin "144") (pinfunction "DIO9_144") (pintype "bidirectional"))
    )
    (net (code "40") (name "DIO10") (class "Default")
      (node (ref "IC3") (pin "9") (pinfunction "IN4_9") (pintype "input"))
      (node (ref "SBRIO_MEZZANINE") (pin "138") (pinfunction "DIO10_138") (pintype "bidirectional"))
    )
    (net (code "41") (name "DIO11") (class "Default")
      (node (ref "IC3") (pin "3") (pinfunction "IN1_3") (pintype "input"))
      (node (ref "SBRIO_MEZZANINE") (pin "126") (pinfunction "DIO11_126") (pintype "bidirectional"))
    )
    (net (code "42") (name "DIO16") (class "Default")
      (node (ref "IC4") (pin "7") (pinfunction "CS_7") (pintype "bidirectional"))
      (node (ref "SBRIO_MEZZANINE") (pin "231") (pinfunction "DIO16_231") (pintype "bidirectional"))
    )
    (net (code "43") (name "DIO17") (class "Default")
      (node (ref "IC4") (pin "9") (pinfunction "INT2_9") (pintype "bidirectional"))
      (node (ref "SBRIO_MEZZANINE") (pin "225") (pinfunction "DIO17_225") (pintype "bidirectional"))
    )
    (net (code "44") (name "DIO18") (class "Default")
      (node (ref "IC4") (pin "13") (pinfunction "SDA_13") (pintype "bidirectional"))
      (node (ref "IC5") (pin "3") (pinfunction "SDA/SDI_3") (pintype "bidirectional"))
      (node (ref "SBRIO_MEZZANINE") (pin "213") (pinfunction "DIO18_213") (pintype "bidirectional"))
    )
    (net (code "45") (name "DIO32") (class "Default")
      (node (ref "IC5") (pin "5") (pinfunction "CS_5") (pintype "bidirectional"))
      (node (ref "SBRIO_MEZZANINE") (pin "221") (pinfunction "DIO32_221") (pintype "bidirectional"))
    )
    (net (code "46") (name "DIO37") (class "Default")
      (node (ref "IC2") (pin "9") (pinfunction "IN4_9") (pintype "input"))
      (node (ref "SBRIO_MEZZANINE") (pin "179") (pinfunction "DIO37_179") (pintype "bidirectional"))
    )
    (net (code "47") (name "DIO38") (class "Default")
      (node (ref "IC2") (pin "3") (pinfunction "IN1_3") (pintype "input"))
      (node (ref "SBRIO_MEZZANINE") (pin "167") (pinfunction "DIO38_167") (pintype "bidirectional"))
    )
    (net (code "48") (name "DIO39") (class "Default")
      (node (ref "C17") (pin "1") (pinfunction "1_1") (pintype "passive"))
      (node (ref "IC11") (pin "P$3") (pinfunction "3.3V_OUT_P$3") (pintype "bidirectional"))
      (node (ref "SBRIO_MEZZANINE") (pin "161") (pinfunction "DIO39_161") (pintype "bidirectional"))
    )
    (net (code "49") (name "DIO40") (class "Default")
      (node (ref "IC1") (pin "7") (pinfunction "IN3_7") (pintype "input"))
      (node (ref "SBRIO_MEZZANINE") (pin "149") (pinfunction "DIO40_149") (pintype "bidirectional"))
    )
    (net (code "50") (name "DIO41") (class "Default")
      (node (ref "IC1") (pin "5") (pinfunction "IN2_5") (pintype "input"))
      (node (ref "SBRIO_MEZZANINE") (pin "143") (pinfunction "DIO41_143") (pintype "bidirectional"))
    )
    (net (code "51") (name "DIO42") (class "Default")
      (node (ref "IC3") (pin "7") (pinfunction "IN3_7") (pintype "input"))
      (node (ref "SBRIO_MEZZANINE") (pin "131") (pinfunction "DIO42_131") (pintype "bidirectional"))
    )
    (net (code "52") (name "DIO43") (class "Default")
      (node (ref "IC3") (pin "5") (pinfunction "IN2_5") (pintype "input"))
      (node (ref "SBRIO_MEZZANINE") (pin "125") (pinfunction "DIO43_125") (pintype "bidirectional"))
    )
    (net (code "53") (name "DIO44") (class "Default")
      (node (ref "R33") (pin "1") (pinfunction "1_1") (pintype "passive"))
      (node (ref "SBRIO_MEZZANINE") (pin "113") (pinfunction "DIO44_113") (pintype "bidirectional"))
    )
    (net (code "54") (name "DIO45") (class "Default")
      (node (ref "R31") (pin "1") (pinfunction "1_1") (pintype "passive"))
      (node (ref "SBRIO_MEZZANINE") (pin "107") (pinfunction "DIO45_107") (pintype "bidirectional"))
    )
    (net (code "55") (name "DIO48") (class "Default")
      (node (ref "IC4") (pin "8") (pinfunction "INT1_8") (pintype "bidirectional"))
      (node (ref "SBRIO_MEZZANINE") (pin "230") (pinfunction "DIO48_230") (pintype "bidirectional"))
    )
    (net (code "56") (name "DIO64") (class "Default")
      (node (ref "IC5") (pin "6") (pinfunction "INT2_6") (pintype "bidirectional"))
      (node (ref "SBRIO_MEZZANINE") (pin "226") (pinfunction "DIO64_226") (pintype "bidirectional"))
    )
    (net (code "57") (name "DIO65") (class "Default")
      (node (ref "IC5") (pin "7") (pinfunction "INT1_7") (pintype "bidirectional"))
      (node (ref "SBRIO_MEZZANINE") (pin "220") (pinfunction "DIO65_220") (pintype "bidirectional"))
    )
    (net (code "58") (name "DIO81") (class "Default")
      (node (ref "IC4") (pin "12") (pinfunction "SDO_12") (pintype "bidirectional"))
      (node (ref "IC5") (pin "4") (pinfunction "SDO_4") (pintype "bidirectional"))
      (node (ref "SBRIO_MEZZANINE") (pin "223") (pinfunction "DIO81_223") (pintype "bidirectional"))
    )
    (net (code "59") (name "DIO83") (class "Default")
      (node (ref "LEVEL_SHIFTER") (pin "8") (pinfunction "OE_8") (pintype "bidirectional"))
      (node (ref "SBRIO_MEZZANINE") (pin "205") (pinfunction "DIO83_205") (pintype "bidirectional"))
    )
    (net (code "60") (name "DIO85") (class "Default")
      (node (ref "LEVEL_SHIFTER") (pin "5") (pinfunction "A4_5") (pintype "bidirectional"))
      (node (ref "SBRIO_MEZZANINE") (pin "187") (pinfunction "DIO85_187") (pintype "bidirectional"))
    )
    (net (code "61") (name "DIO86") (class "Default")
      (node (ref "LEVEL_SHIFTER") (pin "4") (pinfunction "A3_4") (pintype "bidirectional"))
      (node (ref "SBRIO_MEZZANINE") (pin "181") (pinfunction "DIO86_181") (pintype "bidirectional"))
    )
    (net (code "62") (name "DIO87") (class "Default")
      (node (ref "LEVEL_SHIFTER") (pin "3") (pinfunction "A2_3") (pintype "bidirectional"))
      (node (ref "SBRIO_MEZZANINE") (pin "169") (pinfunction "DIO87_169") (pintype "bidirectional"))
    )
    (net (code "63") (name "DIO88") (class "Default")
      (node (ref "LEVEL_SHIFTER") (pin "2") (pinfunction "A1_2") (pintype "bidirectional"))
      (node (ref "SBRIO_MEZZANINE") (pin "163") (pinfunction "DIO88_163") (pintype "bidirectional"))
    )
    (net (code "64") (name "DIO89") (class "Default")
      (node (ref "SBRIO_AUX") (pin "P$12") (pinfunction "DIO18_P$12") (pintype "bidirectional"))
    )
    (net (code "65") (name "DIO90") (class "Default")
      (node (ref "SBRIO_AUX") (pin "P$10") (pinfunction "DIO19_P$10") (pintype "bidirectional"))
      (node (ref "SBRIO_MEZZANINE") (pin "145") (pinfunction "DIO90_145") (pintype "bidirectional"))
    )
    (net (code "66") (name "DIO91") (class "Default")
      (node (ref "SBRIO_AUX") (pin "P$8") (pinfunction "DIO38_P$8") (pintype "bidirectional"))
      (node (ref "SBRIO_MEZZANINE") (pin "133") (pinfunction "DIO91_133") (pintype "bidirectional"))
    )
    (net (code "67") (name "DIO92") (class "Default")
      (node (ref "SBRIO_AUX") (pin "P$5") (pinfunction "DIO15_P$5") (pintype "bidirectional"))
      (node (ref "SBRIO_MEZZANINE") (pin "127") (pinfunction "DIO92_127") (pintype "bidirectional"))
    )
    (net (code "68") (name "DIO93") (class "Default")
      (node (ref "SBRIO_AUX") (pin "P$3") (pinfunction "DIO14_P$3") (pintype "bidirectional"))
      (node (ref "SBRIO_MEZZANINE") (pin "115") (pinfunction "DIO93_115") (pintype "bidirectional"))
    )
    (net (code "69") (name "DIO94") (class "Default")
      (node (ref "C19") (pin "1") (pinfunction "1_1") (pintype "passive"))
      (node (ref "IC9") (pin "P$3") (pinfunction "3.3V_OUT_P$3") (pintype "bidirectional"))
      (node (ref "SBRIO_MEZZANINE") (pin "109") (pinfunction "DIO94_109") (pintype "bidirectional"))
    )
    (net (code "70") (name "DIO95") (class "Default")
      (node (ref "C18") (pin "1") (pinfunction "1_1") (pintype "passive"))
      (node (ref "IC10") (pin "P$3") (pinfunction "3.3V_OUT_P$3") (pintype "bidirectional"))
      (node (ref "SBRIO_MEZZANINE") (pin "97") (pinfunction "DIO95_97") (pintype "bidirectional"))
    )
    (net (code "71") (name "DIO_GND") (class "Default")
      (node (ref "C7") (pin "2") (pinfunction "2_2") (pintype "passive"))
      (node (ref "C8") (pin "2") (pinfunction "2_2") (pintype "passive"))
      (node (ref "IC4") (pin "2") (pinfunction "GND_2") (pintype "bidirectional"))
      (node (ref "IC4") (pin "4") (pinfunction "GND_4") (pintype "bidirectional"))
      (node (ref "IC4") (pin "5") (pinfunction "GND_5") (pintype "bidirectional"))
      (node (ref "SBRIO_ANALOG") (pin "P$1") (pinfunction "AI_GND_P$1") (pintype "input"))
      (node (ref "SBRIO_ANALOG") (pin "P$10") (pinfunction "AI_GND_P$10") (pintype "input"))
      (node (ref "SBRIO_ANALOG") (pin "P$13") (pinfunction "AI_GND_P$13") (pintype "input"))
      (node (ref "SBRIO_ANALOG") (pin "P$16") (pinfunction "AI_GND_P$16") (pintype "input"))
      (node (ref "SBRIO_ANALOG") (pin "P$19") (pinfunction "AI_GND_P$19") (pintype "input"))
      (node (ref "SBRIO_ANALOG") (pin "P$22") (pinfunction "AI_GND_P$22") (pintype "input"))
      (node (ref "SBRIO_ANALOG") (pin "P$25") (pinfunction "AI_GND_P$25") (pintype "input"))
      (node (ref "SBRIO_ANALOG") (pin "P$26") (pinfunction "AI_GND_P$26") (pintype "input"))
      (node (ref "SBRIO_ANALOG") (pin "P$27") (pinfunction "AO_GND_P$27") (pintype "power_in"))
      (node (ref "SBRIO_ANALOG") (pin "P$29") (pinfunction "AO_GND_P$29") (pintype "power_in"))
      (node (ref "SBRIO_ANALOG") (pin "P$31") (pinfunction "AO_GND_P$31") (pintype "power_in"))
      (node (ref "SBRIO_ANALOG") (pin "P$33") (pinfunction "AO_GND_P$33") (pintype "power_in"))
      (node (ref "SBRIO_ANALOG") (pin "P$35") (pinfunction "AO_GND_P$35") (pintype "power_in"))
      (node (ref "SBRIO_ANALOG") (pin "P$37") (pinfunction "AO_GND_P$37") (pintype "power_in"))
      (node (ref "SBRIO_ANALOG") (pin "P$39") (pinfunction "AO_GND_P$39") (pintype "power_in"))
      (node (ref "SBRIO_ANALOG") (pin "P$4") (pinfunction "AI_GND_P$4") (pintype "input"))
      (node (ref "SBRIO_ANALOG") (pin "P$41") (pinfunction "AO_GND_P$41") (pintype "power_in"))
      (node (ref "SBRIO_ANALOG") (pin "P$43") (pinfunction "DIO_GND_P$43") (pintype "power_in"))
      (node (ref "SBRIO_ANALOG") (pin "P$45") (pinfunction "DIO_GND_P$45") (pintype "power_in"))
      (node (ref "SBRIO_ANALOG") (pin "P$47") (pinfunction "DIO_GND_P$47") (pintype "power_in"))
      (node (ref "SBRIO_ANALOG") (pin "P$49") (pinfunction "DIO_GND_P$49") (pintype "power_in"))
      (node (ref "SBRIO_ANALOG") (pin "P$7") (pinfunction "AI_GND_P$7") (pintype "input"))
    )
    (net (code "72") (name "FAN_PWM_OUT") (class "Default")
      (node (ref "IC3") (pin "13") (pinfunction "OUT4_13") (pintype "output"))
      (node (ref "U$4") (pin "P6") (pinfunction "P$6_P6") (pintype "bidirectional"))
    )
    (net (code "73") (name "GND") (class "Default")
      (node (ref "C11") (pin "2") (pinfunction "2_2") (pintype "passive"))
      (node (ref "C12") (pin "2") (pinfunction "2_2") (pintype "passive"))
      (node (ref "C14") (pin "1") (pinfunction "1_1") (pintype "passive"))
      (node (ref "C16") (pin "2") (pinfunction "2_2") (pintype "passive"))
      (node (ref "C17") (pin "2") (pinfunction "2_2") (pintype "passive"))
      (node (ref "C18") (pin "2") (pinfunction "2_2") (pintype "passive"))
      (node (ref "C19") (pin "2") (pinfunction "2_2") (pintype "passive"))
      (node (ref "C20") (pin "2") (pinfunction "2_2") (pintype "passive"))
      (node (ref "C5") (pin "2") (pinfunction "2_2") (pintype "passive"))
      (node (ref "C6") (pin "2") (pinfunction "2_2") (pintype "passive"))
      (node (ref "D7") (pin "P$2") (pinfunction "A_P$2") (pintype "passive"))
      (node (ref "D8") (pin "P$2") (pinfunction "A_P$2") (pintype "passive"))
      (node (ref "IC1") (pin "2") (pinfunction "GND1/2_2") (pintype "input"))
      (node (ref "IC1") (pin "6") (pinfunction "GND3/4_6") (pintype "input"))
      (node (ref "IC10") (pin "P$2") (pinfunction "GND_P$2") (pintype "bidirectional"))
      (node (ref "IC11") (pin "P$2") (pinfunction "GND_P$2") (pintype "bidirectional"))
      (node (ref "IC12") (pin "P$2") (pinfunction "GND_P$2") (pintype "bidirectional"))
      (node (ref "IC2") (pin "2") (pinfunction "GND1/2_2") (pintype "input"))
      (node (ref "IC2") (pin "6") (pinfunction "GND3/4_6") (pintype "input"))
      (node (ref "IC3") (pin "2") (pinfunction "GND1/2_2") (pintype "input"))
      (node (ref "IC3") (pin "6") (pinfunction "GND3/4_6") (pintype "input"))
      (node (ref "IC5") (pin "10") (pinfunction "RSVDG_10") (pintype "bidirectional"))
      (node (ref "IC5") (pin "11") (pinfunction "RSDVG_11") (pintype "bidirectional"))
      (node (ref "IC5") (pin "12") (pinfunction "RSVDG_12") (pintype "bidirectional"))
      (node (ref "IC5") (pin "13") (pinfunction "GND_13") (pintype "bidirectional"))
      (node (ref "IC5") (pin "8") (pinfunction "RSVDG_8") (pintype "bidirectional"))
      (node (ref "IC5") (pin "9") (pinfunction "RSVDG_9") (pintype "bidirectional"))
      (node (ref "IC8") (pin "P$2") (pinfunction "GND_P$2") (pintype "bidirectional"))
      (node (ref "IC9") (pin "P$2") (pinfunction "GND_P$2") (pintype "bidirectional"))
      (node (ref "K1") (pin "C-") (pinfunction "C-_C-") (pintype "passive"))
      (node (ref "K2") (pin "C-") (pinfunction "C-_C-") (pintype "passive"))
      (node (ref "K3") (pin "C-") (pinfunction "C-_C-") (pintype "passive"))
      (node (ref "K4") (pin "C-") (pinfunction "C-_C-") (pintype "passive"))
      (node (ref "K6") (pin "C-") (pinfunction "C-_C-") (pintype "passive"))
      (node (ref "LATCH_U7") (pin "COIL_1") (pinfunction "C_1_COIL_1") (pintype "bidirectional"))
      (node (ref "LEVEL_SHIFTER") (pin "7") (pinfunction "GND_7") (pintype "bidirectional"))
      (node (ref "Q3") (pin "P$3") (pinfunction "E_P$3") (pintype "passive"))
      (node (ref "Q4") (pin "P$3") (pinfunction "E_P$3") (pintype "passive"))
      (node (ref "R15") (pin "2") (pinfunction "2_2") (pintype "passive"))
      (node (ref "R27") (pin "2") (pinfunction "2_2") (pintype "passive"))
      (node (ref "R28") (pin "2") (pinfunction "2_2") (pintype "passive"))
      (node (ref "R29") (pin "2") (pinfunction "2_2") (pintype "passive"))
      (node (ref "R37") (pin "1") (pinfunction "1_1") (pintype "passive"))
      (node (ref "R38") (pin "2") (pinfunction "2_2") (pintype "passive"))
      (node (ref "R39") (pin "2") (pinfunction "2_2") (pintype "passive"))
      (node (ref "R40") (pin "2") (pinfunction "2_2") (pintype "passive"))
      (node (ref "R41") (pin "2") (pinfunction "2_2") (pintype "passive"))
      (node (ref "R42") (pin "2") (pinfunction "2_2") (pintype "passive"))
      (node (ref "R43") (pin "2") (pinfunction "2_2") (pintype "passive"))
      (node (ref "R44") (pin "2") (pinfunction "2_2") (pintype "passive"))
      (node (ref "R45") (pin "2") (pinfunction "2_2") (pintype "passive"))
      (node (ref "R46") (pin "1") (pinfunction "1_1") (pintype "passive"))
      (node (ref "R47") (pin "1") (pinfunction "1_1") (pintype "passive"))
      (node (ref "R48") (pin "1") (pinfunction "1_1") (pintype "passive"))
      (node (ref "R49") (pin "1") (pinfunction "1_1") (pintype "passive"))
      (node (ref "R50") (pin "1") (pinfunction "1_1") (pintype "passive"))
      (node (ref "R51") (pin "1") (pinfunction "1_1") (pintype "passive"))
      (node (ref "R52") (pin "1") (pinfunction "1_1") (pintype "passive"))
      (node (ref "R53") (pin "1") (pinfunction "1_1") (pintype "passive"))
      (node (ref "SBRIO_AUX") (pin "P$11") (pinfunction "GND_P$11") (pintype "bidirectional"))
      (node (ref "SBRIO_AUX") (pin "P$13") (pinfunction "GND_P$13") (pintype "bidirectional"))
      (node (ref "SBRIO_AUX") (pin "P$15") (pinfunction "GND_P$15") (pintype "bidirectional"))
      (node (ref "SBRIO_AUX") (pin "P$17") (pinfunction "GND_P$17") (pintype "bidirectional"))
      (node (ref "SBRIO_AUX") (pin "P$18") (pinfunction "GND_P$18") (pintype "bidirectional"))
      (node (ref "SBRIO_AUX") (pin "P$19") (pinfunction "GND_P$19") (pintype "bidirectional"))
      (node (ref "SBRIO_AUX") (pin "P$20") (pinfunction "GND_P$20") (pintype "bidirectional"))
      (node (ref "SBRIO_AUX") (pin "P$21") (pinfunction "GND_P$21") (pintype "bidirectional"))
      (node (ref "SBRIO_AUX") (pin "P$22") (pinfunction "GND_P$22") (pintype "bidirectional"))
      (node (ref "SBRIO_AUX") (pin "P$23") (pinfunction "GND_P$23") (pintype "bidirectional"))
      (node (ref "SBRIO_AUX") (pin "P$24") (pinfunction "GND_P$24") (pintype "bidirectional"))
      (node (ref "SBRIO_AUX") (pin "P$25") (pinfunction "GND_P$25") (pintype "bidirectional"))
      (node (ref "SBRIO_AUX") (pin "P$26") (pinfunction "GND_P$26") (pintype "bidirectional"))
      (node (ref "SBRIO_AUX") (pin "P$27") (pinfunction "GND_P$27") (pintype "bidirectional"))
      (node (ref "SBRIO_AUX") (pin "P$28") (pinfunction "GND_P$28") (pintype "bidirectional"))
      (node (ref "SBRIO_AUX") (pin "P$29") (pinfunction "GND_P$29") (pintype "bidirectional"))
      (node (ref "SBRIO_AUX") (pin "P$30") (pinfunction "GND_P$30") (pintype "bidirectional"))
      (node (ref "SBRIO_AUX") (pin "P$31") (pinfunction "GND_P$31") (pintype "bidirectional"))
      (node (ref "SBRIO_AUX") (pin "P$32") (pinfunction "GND_P$32") (pintype "bidirectional"))
      (node (ref "SBRIO_AUX") (pin "P$34") (pinfunction "GND_P$34") (pintype "bidirectional"))
      (node (ref "SBRIO_AUX") (pin "P$36") (pinfunction "GND_P$36") (pintype "bidirectional"))
      (node (ref "SBRIO_AUX") (pin "P$38") (pinfunction "GND_P$38") (pintype "bidirectional"))
      (node (ref "SBRIO_AUX") (pin "P$40") (pinfunction "GND_P$40") (pintype "bidirectional"))
      (node (ref "SBRIO_AUX") (pin "P$42") (pinfunction "GND_P$42") (pintype "bidirectional"))
      (node (ref "SBRIO_AUX") (pin "P$44") (pinfunction "GND_P$44") (pintype "bidirectional"))
      (node (ref "SBRIO_AUX") (pin "P$46") (pinfunction "GND_P$46") (pintype "bidirectional"))
      (node (ref "SBRIO_AUX") (pin "P$48") (pinfunction "GND_P$48") (pintype "bidirectional"))
      (node (ref "SBRIO_AUX") (pin "P$50") (pinfunction "GND_P$50") (pintype "bidirectional"))
      (node (ref "SBRIO_AUX") (pin "P$7") (pinfunction "GND_P$7") (pintype "bidirectional"))
      (node (ref "SBRIO_AUX") (pin "P$9") (pinfunction "GND_P$9") (pintype "bidirectional"))
      (node (ref "SBRIO_MEZZANINE") (pin "237") (pinfunction "GND_237") (pintype "power_in"))
      (node (ref "U$1") (pin "P$3") (pinfunction "GND_P$3") (pintype "bidirectional"))
      (node (ref "U$1") (pin "P$6") (pinfunction "GND_P$6") (pintype "bidirectional"))
      (node (ref "U$2") (pin "2") (pinfunction "2_2") (pintype "passive"))
      (node (ref "U$3") (pin "2") (pinfunction "GND_2") (pintype "bidirectional"))
      (node (ref "U$3") (pin "4") (pinfunction "GND_4") (pintype "bidirectional"))
      (node (ref "U$4") (pin "P3") (pinfunction "P$3_P3") (pintype "bidirectional"))
      (node (ref "U$4") (pin "P7") (pinfunction "P$7_P7") (pintype "bidirectional"))
      (node (ref "U$6") (pin "A1") (pinfunction "A1_A1") (pintype "bidirectional"))
      (node (ref "U$6") (pin "A11") (pinfunction "A11_A11") (pintype "bidirectional"))
      (node (ref "U$6") (pin "A13") (pinfunction "A13_A13") (pintype "bidirectional"))
      (node (ref "U$6") (pin "A14") (pinfunction "A14_A14") (pintype "bidirectional"))
      (node (ref "U$6") (pin "A16") (pinfunction "A16_A16") (pintype "bidirectional"))
      (node (ref "U$6") (pin "A17") (pinfunction "A17_A17") (pintype "bidirectional"))
      (node (ref "U$6") (pin "A18") (pinfunction "A18_A18") (pintype "bidirectional"))
      (node (ref "U$6") (pin "A19") (pinfunction "A19_A19") (pintype "bidirectional"))
      (node (ref "U$6") (pin "A20") (pinfunction "A20_A20") (pintype "bidirectional"))
      (node (ref "U$6") (pin "A32") (pinfunction "A32_A32") (pintype "bidirectional"))
      (node (ref "U$6") (pin "B12") (pinfunction "B12_B12") (pintype "bidirectional"))
      (node (ref "U$6") (pin "B13") (pinfunction "B13_B13") (pintype "bidirectional"))
      (node (ref "U$6") (pin "B14") (pinfunction "B14_B14") (pintype "bidirectional"))
      (node (ref "U$6") (pin "B15") (pinfunction "B15_B15") (pintype "bidirectional"))
      (node (ref "U$6") (pin "B16") (pinfunction "B16_B16") (pintype "bidirectional"))
      (node (ref "U$6") (pin "B17") (pinfunction "B17_B17") (pintype "bidirectional"))
      (node (ref "U$6") (pin "B18") (pinfunction "B18_B18") (pintype "bidirectional"))
      (node (ref "U$6") (pin "B19") (pinfunction "B19_B19") (pintype "bidirectional"))
      (node (ref "U$6") (pin "B22") (pinfunction "B22_B22") (pintype "bidirectional"))
      (node (ref "U$6") (pin "B23") (pinfunction "B23_B23") (pintype "bidirectional"))
      (node (ref "U$7") (pin "2") (pinfunction "2_2") (pintype "passive"))
      (node (ref "U$8") (pin "V1") (pinfunction "V1_V1") (pintype "bidirectional"))
      (node (ref "U$9") (pin "P$7") (pinfunction "P$7_P$7") (pintype "bidirectional"))
      (node (ref "U1") (pin "2") (pinfunction "S_2") (pintype "input"))
    )
    (net (code "74") (name "HIGH_CURRENT_IN") (class "Default")
      (node (ref "R2") (pin "2") (pinfunction "2_2") (pintype "passive"))
      (node (ref "R39") (pin "1") (pinfunction "1_1") (pintype "passive"))
      (node (ref "SBRIO_ANALOG") (pin "P$8") (pinfunction "AI2_P$8") (pintype "input"))
      (node (ref "U$6") (pin "B1") (pinfunction "B1_B1") (pintype "bidirectional"))
    )
    (net (code "75") (name "IMD_OK+") (class "Default")
      (node (ref "IC10") (pin "P$1") (pinfunction "3~{16V_IN}_P$1") (pintype "bidirectional"))
      (node (ref "K6") (pin "C+") (pinfunction "C+_C+") (pintype "passive"))
      (node (ref "R27") (pin "1") (pinfunction "1_1") (pintype "passive"))
      (node (ref "U$6") (pin "B3") (pinfunction "B3_B3") (pintype "bidirectional"))
    )
    (net (code "76") (name "INTER_OK+") (class "Default")
      (node (ref "K1") (pin "C+") (pinfunction "C+_C+") (pintype "passive"))
      (node (ref "U$6") (pin "B25") (pinfunction "B25_B25") (pintype "bidirectional"))
    )
    (net (code "77") (name "LATCH_LED+") (class "Default")
      (node (ref "LATCH_U7") (pin "NC_2") (pinfunction "NC_2_NC_2") (pintype "bidirectional"))
      (node (ref "U$9") (pin "P$8") (pinfunction "P$8_P$8") (pintype "bidirectional"))
    )
    (net (code "78") (name "LATCH_SW_IN") (class "Default")
      (node (ref "D7") (pin "P$1") (pinfunction "C_P$1") (pintype "passive"))
      (node (ref "LATCH_U7") (pin "COIL_2") (pinfunction "C_2_COIL_2") (pintype "bidirectional"))
      (node (ref "LATCH_U7") (pin "NO_2") (pinfunction "NO_2_NO_2") (pintype "bidirectional"))
      (node (ref "U$9") (pin "P$6") (pinfunction "P$6_P$6") (pintype "bidirectional"))
    )
    (net (code "79") (name "LATCH_SW_OUT") (class "Default")
      (node (ref "K6") (pin "S2") (pinfunction "SW_2_S2") (pintype "passive"))
      (node (ref "LATCH_U7") (pin "CENTER_2") (pinfunction "IN_2_CENTER_2") (pintype "bidirectional"))
      (node (ref "U$9") (pin "P$5") (pinfunction "P$5_P$5") (pintype "bidirectional"))
    )
    (net (code "80") (name "LOW_CURRENT_IN") (class "Default")
      (node (ref "R53") (pin "2") (pinfunction "2_2") (pintype "passive"))
      (node (ref "SBRIO_ANALOG") (pin "P$6") (pinfunction "AI1_P$6") (pintype "input"))
      (node (ref "U$6") (pin "B2") (pinfunction "B2_B2") (pintype "bidirectional"))
    )
    (net (code "81") (name "Net-(C13-Pad1)") (class "Default")
      (node (ref "C13") (pin "1") (pinfunction "1_1") (pintype "passive"))
      (node (ref "R38") (pin "1") (pinfunction "1_1") (pintype "passive"))
    )
    (net (code "82") (name "Net-(D6-A)") (class "Default")
      (node (ref "D6") (pin "P$2") (pinfunction "A_P$2") (pintype "passive"))
      (node (ref "R37") (pin "2") (pinfunction "2_2") (pintype "passive"))
      (node (ref "SBRIO_ANALOG") (pin "P$2") (pinfunction "AI0_P$2") (pintype "input"))
    )
    (net (code "83") (name "Net-(F2-Pad2)") (class "Default")
      (node (ref "F2") (pin "2") (pinfunction "2_2") (pintype "passive"))
      (node (ref "K3") (pin "C+") (pinfunction "C+_C+") (pintype "passive"))
    )
    (net (code "84") (name "Net-(F3-1-Pad2)") (class "Default")
      (node (ref "F3") (pin "1") (pinfunction "1_1") (pintype "bidirectional"))
      (node (ref "F3") (pin "2") (pinfunction "1_2") (pintype "bidirectional"))
      (node (ref "U$8") (pin "A") (pinfunction "A_A") (pintype "bidirectional"))
    )
    (net (code "85") (name "Net-(F5-Pad2)") (class "Default")
      (node (ref "F5") (pin "2") (pinfunction "2_2") (pintype "passive"))
      (node (ref "U$6") (pin "A29") (pinfunction "A29_A29") (pintype "bidirectional"))
    )
    (net (code "86") (name "Net-(F7-Pad2)") (class "Default")
      (node (ref "F7") (pin "2") (pinfunction "2_2") (pintype "passive"))
      (node (ref "U$6") (pin "A28") (pinfunction "A28_A28") (pintype "bidirectional"))
    )
    (net (code "87") (name "Net-(F8-Pad2)") (class "Default")
      (node (ref "F8") (pin "2") (pinfunction "2_2") (pintype "passive"))
      (node (ref "U$6") (pin "A27") (pinfunction "A27_A27") (pintype "bidirectional"))
    )
    (net (code "88") (name "Net-(F9-Pad2)") (class "Default")
      (node (ref "F9") (pin "2") (pinfunction "2_2") (pintype "passive"))
      (node (ref "U$6") (pin "A26") (pinfunction "A26_A26") (pintype "bidirectional"))
    )
    (net (code "89") (name "Net-(F14-Pad2)") (class "Default")
      (node (ref "F14") (pin "2") (pinfunction "2_2") (pintype "passive"))
      (node (ref "K2") (pin "C+") (pinfunction "C+_C+") (pintype "passive"))
    )
    (net (code "90") (name "Net-(IC5-PLL)") (class "Default")
      (node (ref "C13") (pin "2") (pinfunction "2_2") (pintype "passive"))
      (node (ref "C14") (pin "2") (pinfunction "2_2") (pintype "passive"))
      (node (ref "IC5") (pin "14") (pinfunction "PLL_14") (pintype "bidirectional"))
    )
    (net (code "91") (name "Net-(IC9-3~{16V_IN})") (class "Default")
      (node (ref "IC9") (pin "P$1") (pinfunction "3~{16V_IN}_P$1") (pintype "bidirectional"))
      (node (ref "R6") (pin "2") (pinfunction "2_2") (pintype "passive"))
      (node (ref "U1") (pin "3") (pinfunction "D_3") (pintype "output"))
    )
    (net (code "92") (name "Net-(K1-SW_1)") (class "Default")
      (node (ref "K1") (pin "S1") (pinfunction "SW_1_S1") (pintype "passive"))
      (node (ref "K2") (pin "S2") (pinfunction "SW_2_S2") (pintype "passive"))
    )
    (net (code "93") (name "Net-(K2-SW_1)") (class "Default")
      (node (ref "K2") (pin "S1") (pinfunction "SW_1_S1") (pintype "passive"))
      (node (ref "K3") (pin "S2") (pinfunction "SW_2_S2") (pintype "passive"))
    )
    (net (code "94") (name "Net-(K4-SW_2)") (class "Default")
      (node (ref "K4") (pin "S2") (pinfunction "SW_2_S2") (pintype "passive"))
      (node (ref "K5") (pin "S1") (pinfunction "SW_1_S1") (pintype "passive"))
    )
    (net (code "95") (name "Net-(K5-SW_2)") (class "Default")
      (node (ref "K5") (pin "S2") (pinfunction "SW_2_S2") (pintype "passive"))
      (node (ref "K6") (pin "S1") (pinfunction "SW_1_S1") (pintype "passive"))
    )
    (net (code "96") (name "Net-(Q1-B)") (class "Default")
      (node (ref "Q1") (pin "P$2") (pinfunction "B_P$2") (pintype "passive"))
      (node (ref "R34") (pin "2") (pinfunction "2_2") (pintype "passive"))
    )
    (net (code "97") (name "Net-(Q1-C)") (class "Default")
      (node (ref "F17") (pin "2") (pinfunction "2_2") (pintype "passive"))
      (node (ref "Q1") (pin "P$1") (pinfunction "C_P$1") (pintype "passive"))
    )
    (net (code "98") (name "Net-(Q2-B)") (class "Default")
      (node (ref "Q2") (pin "P$2") (pinfunction "B_P$2") (pintype "passive"))
      (node (ref "R32") (pin "2") (pinfunction "2_2") (pintype "passive"))
    )
    (net (code "99") (name "Net-(Q2-C)") (class "Default")
      (node (ref "F18") (pin "2") (pinfunction "2_2") (pintype "passive"))
      (node (ref "Q2") (pin "P$1") (pinfunction "C_P$1") (pintype "passive"))
    )
    (net (code "100") (name "Net-(Q3-B)") (class "Default")
      (node (ref "Q3") (pin "P$2") (pinfunction "B_P$2") (pintype "passive"))
      (node (ref "R33") (pin "2") (pinfunction "2_2") (pintype "passive"))
    )
    (net (code "101") (name "Net-(Q3-C)") (class "Default")
      (node (ref "Q3") (pin "P$1") (pinfunction "C_P$1") (pintype "passive"))
      (node (ref "R34") (pin "1") (pinfunction "1_1") (pintype "passive"))
    )
    (net (code "102") (name "Net-(Q4-B)") (class "Default")
      (node (ref "Q4") (pin "P$2") (pinfunction "B_P$2") (pintype "passive"))
      (node (ref "R31") (pin "2") (pinfunction "2_2") (pintype "passive"))
    )
    (net (code "103") (name "Net-(Q4-C)") (class "Default")
      (node (ref "Q4") (pin "P$1") (pinfunction "C_P$1") (pintype "passive"))
      (node (ref "R32") (pin "1") (pinfunction "1_1") (pintype "passive"))
    )
    (net (code "104") (name "Net-(U$10-2)") (class "Default")
      (node (ref "R1") (pin "1") (pinfunction "1_1") (pintype "passive"))
      (node (ref "U$10") (pin "P2") (pinfunction "2_P2") (pintype "bidirectional"))
    )
    (net (code "105") (name "Net-(U$10-3)") (class "Default")
      (node (ref "R2") (pin "1") (pinfunction "1_1") (pintype "passive"))
      (node (ref "U$10") (pin "P3") (pinfunction "3_P3") (pintype "bidirectional"))
    )
    (net (code "106") (name "Net-(U$10-4)") (class "Default")
      (node (ref "R3") (pin "1") (pinfunction "1_1") (pintype "passive"))
      (node (ref "U$10") (pin "P4") (pinfunction "4_P4") (pintype "bidirectional"))
    )
    (net (code "107") (name "Net-(U$10-5)") (class "Default")
      (node (ref "R4") (pin "1") (pinfunction "1_1") (pintype "passive"))
      (node (ref "U$10") (pin "P5") (pinfunction "5_P5") (pintype "bidirectional"))
    )
    (net (code "108") (name "Net-(U$10-6)") (class "Default")
      (node (ref "R5") (pin "1") (pinfunction "1_1") (pintype "passive"))
      (node (ref "U$10") (pin "P6") (pinfunction "6_P6") (pintype "bidirectional"))
    )
    (net (code "109") (name "PO3") (class "Default")
      (node (ref "IC1") (pin "14") (pinfunction "OUT3_14") (pintype "output"))
      (node (ref "K5") (pin "C+") (pinfunction "C+_C+") (pintype "passive"))
    )
    (net (code "110") (name "POSITIVE_AIR_ENABLE") (class "Default")
      (node (ref "IC3") (pin "14") (pinfunction "OUT3_14") (pintype "output"))
      (node (ref "U$6") (pin "B8") (pinfunction "B8_B8") (pintype "bidirectional"))
    )
    (net (code "111") (name "PRECHARGE_DONE+") (class "Default")
      (node (ref "IC1") (pin "13") (pinfunction "OUT4_13") (pintype "output"))
      (node (ref "U$6") (pin "B24") (pinfunction "B24_B24") (pintype "bidirectional"))
    )
    (net (code "112") (name "SBRIO_OK+_1") (class "Default")
      (node (ref "F2") (pin "1") (pinfunction "1_1") (pintype "passive"))
      (node (ref "IC2") (pin "14") (pinfunction "OUT3_14") (pintype "output"))
    )
    (net (code "113") (name "SBRIO_OK+_2") (class "Default")
      (node (ref "F14") (pin "1") (pinfunction "1_1") (pintype "passive"))
      (node (ref "IC2") (pin "17") (pinfunction "OUT2_17") (pintype "output"))
    )
    (net (code "114") (name "SHUTDOWN_3") (class "Default")
      (node (ref "IC2") (pin "13") (pinfunction "OUT4_13") (pintype "output"))
    )
    (net (code "115") (name "SHUTDOWN_OK+") (class "Default")
      (node (ref "K1") (pin "S2") (pinfunction "SW_2_S2") (pintype "passive"))
      (node (ref "LATCH_U7") (pin "NO_1") (pinfunction "NO_1_NO_1") (pintype "bidirectional"))
    )
    (net (code "116") (name "SIGNAL_GND") (class "Default")
      (node (ref "U$10") (pin "P1") (pinfunction "1_P1") (pintype "bidirectional"))
      (node (ref "U$4") (pin "P2") (pinfunction "P$2_P2") (pintype "bidirectional"))
      (node (ref "U$6") (pin "B5") (pinfunction "B5_B5") (pintype "bidirectional"))
    )
    (net (code "117") (name "STEERING_POS") (class "Default")
      (node (ref "R45") (pin "1") (pinfunction "1_1") (pintype "passive"))
      (node (ref "SBRIO_ANALOG") (pin "P$21") (pinfunction "AI14_P$21") (pintype "input"))
      (node (ref "SBRIO_AUX") (pin "P$39") (pinfunction "AI14_P$39") (pintype "bidirectional"))
      (node (ref "U$6") (pin "A31") (pinfunction "A31_A31") (pintype "bidirectional"))
    )
    (net (code "118") (name "THROTTLE_IN_1") (class "Default")
      (node (ref "R51") (pin "2") (pinfunction "2_2") (pintype "passive"))
      (node (ref "SBRIO_ANALOG") (pin "P$18") (pinfunction "AI5_P$18") (pintype "input"))
      (node (ref "U$6") (pin "A8") (pinfunction "A8_A8") (pintype "bidirectional"))
    )
    (net (code "119") (name "THROTTLE_IN_2") (class "Default")
      (node (ref "R41") (pin "1") (pinfunction "1_1") (pintype "passive"))
      (node (ref "SBRIO_ANALOG") (pin "P$20") (pinfunction "AI6_P$20") (pintype "input"))
      (node (ref "U$6") (pin "A21") (pinfunction "A21_A21") (pintype "bidirectional"))
    )
    (net (code "120") (name "THROTTLE_OK_OUT") (class "Default")
      (node (ref "IC2") (pin "18") (pinfunction "OUT1_18") (pintype "output"))
    )
    (net (code "121") (name "TSMS_IN+") (class "Default")
      (node (ref "IC11") (pin "P$1") (pinfunction "3~{16V_IN}_P$1") (pintype "bidirectional"))
      (node (ref "R28") (pin "1") (pinfunction "1_1") (pintype "passive"))
      (node (ref "U$6") (pin "A15") (pinfunction "A15_A15") (pintype "bidirectional"))
      (node (ref "U$6") (pin "B10") (pinfunction "B10_B10") (pintype "bidirectional"))
    )
    (net (code "122") (name "TSMS_OUT+") (class "Default")
      (node (ref "IC8") (pin "P$1") (pinfunction "3~{16V_IN}_P$1") (pintype "bidirectional"))
      (node (ref "R15") (pin "1") (pinfunction "1_1") (pintype "passive"))
      (node (ref "U$6") (pin "A3") (pinfunction "A3_A3") (pintype "bidirectional"))
      (node (ref "U$8") (pin "CENTER") (pinfunction "C_CENTER") (pintype "bidirectional"))
    )
    (net (code "123") (name "TSMS_OUT_CTRL+") (class "Default")
      (node (ref "D8") (pin "P$1") (pinfunction "C_P$1") (pintype "passive"))
      (node (ref "LATCH_U7") (pin "CENTER_1") (pinfunction "IN_1_CENTER_1") (pintype "bidirectional"))
      (node (ref "U$8") (pin "V2") (pinfunction "V2_V2") (pintype "bidirectional"))
    )
    (net (code "124") (name "WS1") (class "Default")
      (node (ref "LEVEL_SHIFTER") (pin "13") (pinfunction "B1_13") (pintype "bidirectional"))
      (node (ref "U$6") (pin "A22") (pinfunction "A22_A22") (pintype "bidirectional"))
    )
    (net (code "125") (name "WS2") (class "Default")
      (node (ref "LEVEL_SHIFTER") (pin "12") (pinfunction "B2_12") (pintype "bidirectional"))
      (node (ref "U$6") (pin "A23") (pinfunction "A23_A23") (pintype "bidirectional"))
    )
    (net (code "126") (name "WS3") (class "Default")
      (node (ref "LEVEL_SHIFTER") (pin "11") (pinfunction "B3_11") (pintype "bidirectional"))
      (node (ref "U$6") (pin "A24") (pinfunction "A24_A24") (pintype "bidirectional"))
    )
    (net (code "127") (name "WS4") (class "Default")
      (node (ref "LEVEL_SHIFTER") (pin "10") (pinfunction "B4_10") (pintype "bidirectional"))
      (node (ref "U$6") (pin "A25") (pinfunction "A25_A25") (pintype "bidirectional"))
    )
    (net (code "128") (name "unconnected-(IC1A-ST1{slash}2-Pad4)") (class "Default")
      (node (ref "IC1") (pin "4") (pinfunction "ST1/2_4") (pintype "input"))
    )
    (net (code "129") (name "unconnected-(IC1A-ST3{slash}4-Pad8)") (class "Default")
      (node (ref "IC1") (pin "8") (pinfunction "ST3/4_8") (pintype "input"))
    )
    (net (code "130") (name "unconnected-(IC2A-ST1{slash}2-Pad4)") (class "Default")
      (node (ref "IC2") (pin "4") (pinfunction "ST1/2_4") (pintype "input"))
    )
    (net (code "131") (name "unconnected-(IC2A-ST3{slash}4-Pad8)") (class "Default")
      (node (ref "IC2") (pin "8") (pinfunction "ST3/4_8") (pintype "input"))
    )
    (net (code "132") (name "unconnected-(IC3A-ST1{slash}2-Pad4)") (class "Default")
      (node (ref "IC3") (pin "4") (pinfunction "ST1/2_4") (pintype "input"))
    )
    (net (code "133") (name "unconnected-(IC3A-ST3{slash}4-Pad8)") (class "Default")
      (node (ref "IC3") (pin "8") (pinfunction "ST3/4_8") (pintype "input"))
    )
    (net (code "134") (name "unconnected-(IC4-NC-Pad3)") (class "Default")
      (node (ref "IC4") (pin "3") (pinfunction "NC_3") (pintype "bidirectional"))
    )
    (net (code "135") (name "unconnected-(IC4-NC-Pad10)") (class "Default")
      (node (ref "IC4") (pin "10") (pinfunction "NC_10") (pintype "bidirectional"))
    )
    (net (code "136") (name "unconnected-(IC4-NC-Pad11)") (class "Default")
      (node (ref "IC4") (pin "11") (pinfunction "NC_11") (pintype "bidirectional"))
    )
    (net (code "137") (name "unconnected-(LATCH_U7-PadNC_1)") (class "Default")
      (node (ref "LATCH_U7") (pin "NC_1") (pinfunction "NC_1_NC_1") (pintype "bidirectional"))
    )
    (net (code "138") (name "unconnected-(SBRIO_ANALOG-DIO_0-PadP$44)") (class "Default")
      (node (ref "SBRIO_ANALOG") (pin "P$44") (pinfunction "DIO_0_P$44") (pintype "bidirectional"))
    )
    (net (code "139") (name "unconnected-(SBRIO_ANALOG-DIO_1-PadP$46)") (class "Default")
      (node (ref "SBRIO_ANALOG") (pin "P$46") (pinfunction "DIO_1_P$46") (pintype "bidirectional"))
    )
    (net (code "140") (name "unconnected-(SBRIO_ANALOG-DIO_2-PadP$48)") (class "Default")
      (node (ref "SBRIO_ANALOG") (pin "P$48") (pinfunction "DIO_2_P$48") (pintype "bidirectional"))
    )
    (net (code "141") (name "unconnected-(SBRIO_ANALOG-DIO_3-PadP$50)") (class "Default")
      (node (ref "SBRIO_ANALOG") (pin "P$50") (pinfunction "DIO_3_P$50") (pintype "bidirectional"))
    )
    (net (code "142") (name "unconnected-(SBRIO_AUX-DIO16-PadP$16)") (class "Default")
      (node (ref "SBRIO_AUX") (pin "P$16") (pinfunction "DIO16_P$16") (pintype "bidirectional"))
    )
    (net (code "143") (name "unconnected-(SBRIO_AUX-DIO17-PadP$14)") (class "Default")
      (node (ref "SBRIO_AUX") (pin "P$14") (pinfunction "DIO17_P$14") (pintype "bidirectional"))
    )
    (net (code "144") (name "unconnected-(SBRIO_AUX-DIO39-PadP$6)") (class "Default")
      (node (ref "SBRIO_AUX") (pin "P$6") (pinfunction "DIO39_P$6") (pintype "bidirectional"))
    )
    (net (code "145") (name "unconnected-(SBRIO_AUX-E-STOP-PadP$4)") (class "Default")
      (node (ref "SBRIO_AUX") (pin "P$4") (pinfunction "E-STOP_P$4") (pintype "bidirectional"))
    )
    (net (code "146") (name "unconnected-(SBRIO_AUX-LATCH-PadP$2)") (class "Default")
      (node (ref "SBRIO_AUX") (pin "P$2") (pinfunction "LATCH_P$2") (pintype "bidirectional"))
    )
    (net (code "147") (name "unconnected-(SBRIO_AUX-POS_AIR-PadP$1)") (class "Default")
      (node (ref "SBRIO_AUX") (pin "P$1") (pinfunction "POS_AIR_P$1") (pintype "bidirectional"))
    )
    (net (code "148") (name "unconnected-(SBRIO_MEZZANINE-DIO2-Pad210)") (class "Default")
      (node (ref "SBRIO_MEZZANINE") (pin "210") (pinfunction "DIO2_210") (pintype "bidirectional"))
    )
    (net (code "149") (name "unconnected-(SBRIO_MEZZANINE-DIO3-Pad198)") (class "Default")
      (node (ref "SBRIO_MEZZANINE") (pin "198") (pinfunction "DIO3_198") (pintype "bidirectional"))
    )
    (net (code "150") (name "unconnected-(SBRIO_MEZZANINE-DIO4-Pad192)") (class "Default")
      (node (ref "SBRIO_MEZZANINE") (pin "192") (pinfunction "DIO4_192") (pintype "bidirectional"))
    )
    (net (code "151") (name "unconnected-(SBRIO_MEZZANINE-DIO12-Pad120)") (class "Default")
      (node (ref "SBRIO_MEZZANINE") (pin "120") (pinfunction "DIO12_120") (pintype "bidirectional"))
    )
    (net (code "152") (name "unconnected-(SBRIO_MEZZANINE-DIO13-Pad108)") (class "Default")
      (node (ref "SBRIO_MEZZANINE") (pin "108") (pinfunction "DIO13_108") (pintype "bidirectional"))
    )
    (net (code "153") (name "unconnected-(SBRIO_MEZZANINE-DIO14-Pad102)") (class "Default")
      (node (ref "SBRIO_MEZZANINE") (pin "102") (pinfunction "DIO14_102") (pintype "bidirectional"))
    )
    (net (code "154") (name "unconnected-(SBRIO_MEZZANINE-DIO15-Pad90)") (class "Default")
      (node (ref "SBRIO_MEZZANINE") (pin "90") (pinfunction "DIO15_90") (pintype "bidirectional"))
    )
    (net (code "155") (name "unconnected-(SBRIO_MEZZANINE-DIO19-Pad207)") (class "Default")
      (node (ref "SBRIO_MEZZANINE") (pin "207") (pinfunction "DIO19_207") (pintype "bidirectional"))
    )
    (net (code "156") (name "unconnected-(SBRIO_MEZZANINE-DIO20-Pad195)") (class "Default")
      (node (ref "SBRIO_MEZZANINE") (pin "195") (pinfunction "DIO20_195") (pintype "bidirectional"))
    )
    (net (code "157") (name "unconnected-(SBRIO_MEZZANINE-DIO21-Pad189)") (class "Default")
      (node (ref "SBRIO_MEZZANINE") (pin "189") (pinfunction "DIO21_189") (pintype "bidirectional"))
    )
    (net (code "158") (name "unconnected-(SBRIO_MEZZANINE-DIO22-Pad177)") (class "Default")
      (node (ref "SBRIO_MEZZANINE") (pin "177") (pinfunction "DIO22_177") (pintype "bidirectional"))
    )
    (net (code "159") (name "unconnected-(SBRIO_MEZZANINE-DIO23-Pad171)") (class "Default")
      (node (ref "SBRIO_MEZZANINE") (pin "171") (pinfunction "DIO23_171") (pintype "bidirectional"))
    )
    (net (code "160") (name "unconnected-(SBRIO_MEZZANINE-DIO24-Pad159)") (class "Default")
      (node (ref "SBRIO_MEZZANINE") (pin "159") (pinfunction "DIO24_159") (pintype "bidirectional"))
    )
    (net (code "161") (name "unconnected-(SBRIO_MEZZANINE-DIO25-Pad153)") (class "Default")
      (node (ref "SBRIO_MEZZANINE") (pin "153") (pinfunction "DIO25_153") (pintype "bidirectional"))
    )
    (net (code "162") (name "unconnected-(SBRIO_MEZZANINE-DIO26-Pad141)") (class "Default")
      (node (ref "SBRIO_MEZZANINE") (pin "141") (pinfunction "DIO26_141") (pintype "bidirectional"))
    )
    (net (code "163") (name "unconnected-(SBRIO_MEZZANINE-DIO27-Pad135)") (class "Default")
      (node (ref "SBRIO_MEZZANINE") (pin "135") (pinfunction "DIO27_135") (pintype "bidirectional"))
    )
    (net (code "164") (name "unconnected-(SBRIO_MEZZANINE-DIO28-Pad123)") (class "Default")
      (node (ref "SBRIO_MEZZANINE") (pin "123") (pinfunction "DIO28_123") (pintype "bidirectional"))
    )
    (net (code "165") (name "unconnected-(SBRIO_MEZZANINE-DIO29-Pad117)") (class "Default")
      (node (ref "SBRIO_MEZZANINE") (pin "117") (pinfunction "DIO29_117") (pintype "bidirectional"))
    )
    (net (code "166") (name "unconnected-(SBRIO_MEZZANINE-DIO30-Pad105)") (class "Default")
      (node (ref "SBRIO_MEZZANINE") (pin "105") (pinfunction "DIO30_105") (pintype "bidirectional"))
    )
    (net (code "167") (name "unconnected-(SBRIO_MEZZANINE-DIO31-Pad99)") (class "Default")
      (node (ref "SBRIO_MEZZANINE") (pin "99") (pinfunction "DIO31_99") (pintype "bidirectional"))
    )
    (net (code "168") (name "unconnected-(SBRIO_MEZZANINE-DIO33-Pad215)") (class "Default")
      (node (ref "SBRIO_MEZZANINE") (pin "215") (pinfunction "DIO33_215") (pintype "bidirectional"))
    )
    (net (code "169") (name "unconnected-(SBRIO_MEZZANINE-DIO34-Pad203)") (class "Default")
      (node (ref "SBRIO_MEZZANINE") (pin "203") (pinfunction "DIO34_203") (pintype "bidirectional"))
    )
    (net (code "170") (name "unconnected-(SBRIO_MEZZANINE-DIO35-Pad197)") (class "Default")
      (node (ref "SBRIO_MEZZANINE") (pin "197") (pinfunction "DIO35_197") (pintype "bidirectional"))
    )
    (net (code "171") (name "unconnected-(SBRIO_MEZZANINE-DIO36-Pad185)") (class "Default")
      (node (ref "SBRIO_MEZZANINE") (pin "185") (pinfunction "DIO36_185") (pintype "bidirectional"))
    )
    (net (code "172") (name "unconnected-(SBRIO_MEZZANINE-DIO46-Pad95)") (class "Default")
      (node (ref "SBRIO_MEZZANINE") (pin "95") (pinfunction "DIO46_95") (pintype "bidirectional"))
    )
    (net (code "173") (name "unconnected-(SBRIO_MEZZANINE-DIO47-Pad89)") (class "Default")
      (node (ref "SBRIO_MEZZANINE") (pin "89") (pinfunction "DIO47_89") (pintype "bidirectional"))
    )
    (net (code "174") (name "unconnected-(SBRIO_MEZZANINE-DIO49-Pad218)") (class "Default")
      (node (ref "SBRIO_MEZZANINE") (pin "218") (pinfunction "DIO49_218") (pintype "bidirectional"))
    )
    (net (code "175") (name "unconnected-(SBRIO_MEZZANINE-DIO50-Pad212)") (class "Default")
      (node (ref "SBRIO_MEZZANINE") (pin "212") (pinfunction "DIO50_212") (pintype "bidirectional"))
    )
    (net (code "176") (name "unconnected-(SBRIO_MEZZANINE-DIO51-Pad200)") (class "Default")
      (node (ref "SBRIO_MEZZANINE") (pin "200") (pinfunction "DIO51_200") (pintype "bidirectional"))
    )
    (net (code "177") (name "unconnected-(SBRIO_MEZZANINE-DIO52-Pad194)") (class "Default")
      (node (ref "SBRIO_MEZZANINE") (pin "194") (pinfunction "DIO52_194") (pintype "bidirectional"))
    )
    (net (code "178") (name "unconnected-(SBRIO_MEZZANINE-DIO53-Pad182)") (class "Default")
      (node (ref "SBRIO_MEZZANINE") (pin "182") (pinfunction "DIO53_182") (pintype "bidirectional"))
    )
    (net (code "179") (name "unconnected-(SBRIO_MEZZANINE-DIO54-Pad176)") (class "Default")
      (node (ref "SBRIO_MEZZANINE") (pin "176") (pinfunction "DIO54_176") (pintype "bidirectional"))
    )
    (net (code "180") (name "unconnected-(SBRIO_MEZZANINE-DIO55-Pad164)") (class "Default")
      (node (ref "SBRIO_MEZZANINE") (pin "164") (pinfunction "DIO55_164") (pintype "bidirectional"))
    )
    (net (code "181") (name "unconnected-(SBRIO_MEZZANINE-DIO56-Pad158)") (class "Default")
      (node (ref "SBRIO_MEZZANINE") (pin "158") (pinfunction "DIO56_158") (pintype "bidirectional"))
    )
    (net (code "182") (name "unconnected-(SBRIO_MEZZANINE-DIO57-Pad146)") (class "Default")
      (node (ref "SBRIO_MEZZANINE") (pin "146") (pinfunction "DIO57_146") (pintype "bidirectional"))
    )
    (net (code "183") (name "unconnected-(SBRIO_MEZZANINE-DIO58-Pad140)") (class "Default")
      (node (ref "SBRIO_MEZZANINE") (pin "140") (pinfunction "DIO58_140") (pintype "bidirectional"))
    )
    (net (code "184") (name "unconnected-(SBRIO_MEZZANINE-DIO59-Pad128)") (class "Default")
      (node (ref "SBRIO_MEZZANINE") (pin "128") (pinfunction "DIO59_128") (pintype "bidirectional"))
    )
    (net (code "185") (name "unconnected-(SBRIO_MEZZANINE-DIO60-Pad122)") (class "Default")
      (node (ref "SBRIO_MEZZANINE") (pin "122") (pinfunction "DIO60_122") (pintype "bidirectional"))
    )
    (net (code "186") (name "unconnected-(SBRIO_MEZZANINE-DIO61-Pad110)") (class "Default")
      (node (ref "SBRIO_MEZZANINE") (pin "110") (pinfunction "DIO61_110") (pintype "bidirectional"))
    )
    (net (code "187") (name "unconnected-(SBRIO_MEZZANINE-DIO62-Pad104)") (class "Default")
      (node (ref "SBRIO_MEZZANINE") (pin "104") (pinfunction "DIO62_104") (pintype "bidirectional"))
    )
    (net (code "188") (name "unconnected-(SBRIO_MEZZANINE-DIO63-Pad92)") (class "Default")
      (node (ref "SBRIO_MEZZANINE") (pin "92") (pinfunction "DIO63_92") (pintype "bidirectional"))
    )
    (net (code "189") (name "unconnected-(SBRIO_MEZZANINE-DIO66-Pad208)") (class "Default")
      (node (ref "SBRIO_MEZZANINE") (pin "208") (pinfunction "DIO66_208") (pintype "bidirectional"))
    )
    (net (code "190") (name "unconnected-(SBRIO_MEZZANINE-DIO67-Pad202)") (class "Default")
      (node (ref "SBRIO_MEZZANINE") (pin "202") (pinfunction "DIO67_202") (pintype "bidirectional"))
    )
    (net (code "191") (name "unconnected-(SBRIO_MEZZANINE-DIO68-Pad190)") (class "Default")
      (node (ref "SBRIO_MEZZANINE") (pin "190") (pinfunction "DIO68_190") (pintype "bidirectional"))
    )
    (net (code "192") (name "unconnected-(SBRIO_MEZZANINE-DIO69-Pad184)") (class "Default")
      (node (ref "SBRIO_MEZZANINE") (pin "184") (pinfunction "DIO69_184") (pintype "bidirectional"))
    )
    (net (code "193") (name "unconnected-(SBRIO_MEZZANINE-DIO70-Pad172)") (class "Default")
      (node (ref "SBRIO_MEZZANINE") (pin "172") (pinfunction "DIO70_172") (pintype "bidirectional"))
    )
    (net (code "194") (name "unconnected-(SBRIO_MEZZANINE-DIO71-Pad166)") (class "Default")
      (node (ref "SBRIO_MEZZANINE") (pin "166") (pinfunction "DIO71_166") (pintype "bidirectional"))
    )
    (net (code "195") (name "unconnected-(SBRIO_MEZZANINE-DIO72-Pad154)") (class "Default")
      (node (ref "SBRIO_MEZZANINE") (pin "154") (pinfunction "DIO72_154") (pintype "bidirectional"))
    )
    (net (code "196") (name "unconnected-(SBRIO_MEZZANINE-DIO73-Pad148)") (class "Default")
      (node (ref "SBRIO_MEZZANINE") (pin "148") (pinfunction "DIO73_148") (pintype "bidirectional"))
    )
    (net (code "197") (name "unconnected-(SBRIO_MEZZANINE-DIO74-Pad136)") (class "Default")
      (node (ref "SBRIO_MEZZANINE") (pin "136") (pinfunction "DIO74_136") (pintype "bidirectional"))
    )
    (net (code "198") (name "unconnected-(SBRIO_MEZZANINE-DIO75-Pad130)") (class "Default")
      (node (ref "SBRIO_MEZZANINE") (pin "130") (pinfunction "DIO75_130") (pintype "bidirectional"))
    )
    (net (code "199") (name "unconnected-(SBRIO_MEZZANINE-DIO76-Pad118)") (class "Default")
      (node (ref "SBRIO_MEZZANINE") (pin "118") (pinfunction "DIO76_118") (pintype "bidirectional"))
    )
    (net (code "200") (name "unconnected-(SBRIO_MEZZANINE-DIO77-Pad112)") (class "Default")
      (node (ref "SBRIO_MEZZANINE") (pin "112") (pinfunction "DIO77_112") (pintype "bidirectional"))
    )
    (net (code "201") (name "unconnected-(SBRIO_MEZZANINE-DIO78-Pad100)") (class "Default")
      (node (ref "SBRIO_MEZZANINE") (pin "100") (pinfunction "DIO78_100") (pintype "bidirectional"))
    )
    (net (code "202") (name "unconnected-(SBRIO_MEZZANINE-DIO79-Pad94)") (class "Default")
      (node (ref "SBRIO_MEZZANINE") (pin "94") (pinfunction "DIO79_94") (pintype "bidirectional"))
    )
    (net (code "203") (name "unconnected-(SBRIO_MEZZANINE-DIO80-Pad235)") (class "Default")
      (node (ref "SBRIO_MEZZANINE") (pin "235") (pinfunction "DIO80_235") (pintype "bidirectional"))
    )
    (net (code "204") (name "unconnected-(SBRIO_MEZZANINE-DIO82-Pad217)") (class "Default")
      (node (ref "SBRIO_MEZZANINE") (pin "217") (pinfunction "DIO82_217") (pintype "bidirectional"))
    )
    (net (code "205") (name "unconnected-(SBRIO_MEZZANINE-DIO84-Pad199)") (class "Default")
      (node (ref "SBRIO_MEZZANINE") (pin "199") (pinfunction "DIO84_199") (pintype "bidirectional"))
    )
    (net (code "206") (name "unconnected-(SBRIO_MEZZANINE-DIO89-Pad151)") (class "Default")
      (node (ref "SBRIO_MEZZANINE") (pin "151") (pinfunction "DIO89_151") (pintype "bidirectional"))
    )
    (net (code "207") (name "unconnected-(U$8-PadB)") (class "Default")
      (node (ref "U$8") (pin "B") (pinfunction "B_B") (pintype "bidirectional"))
    )
  )
)
